# RFFI_pwrCtrl_Integrated_2021-05-11.net
KiCad netlist of a schematic drawn in EasyEDA
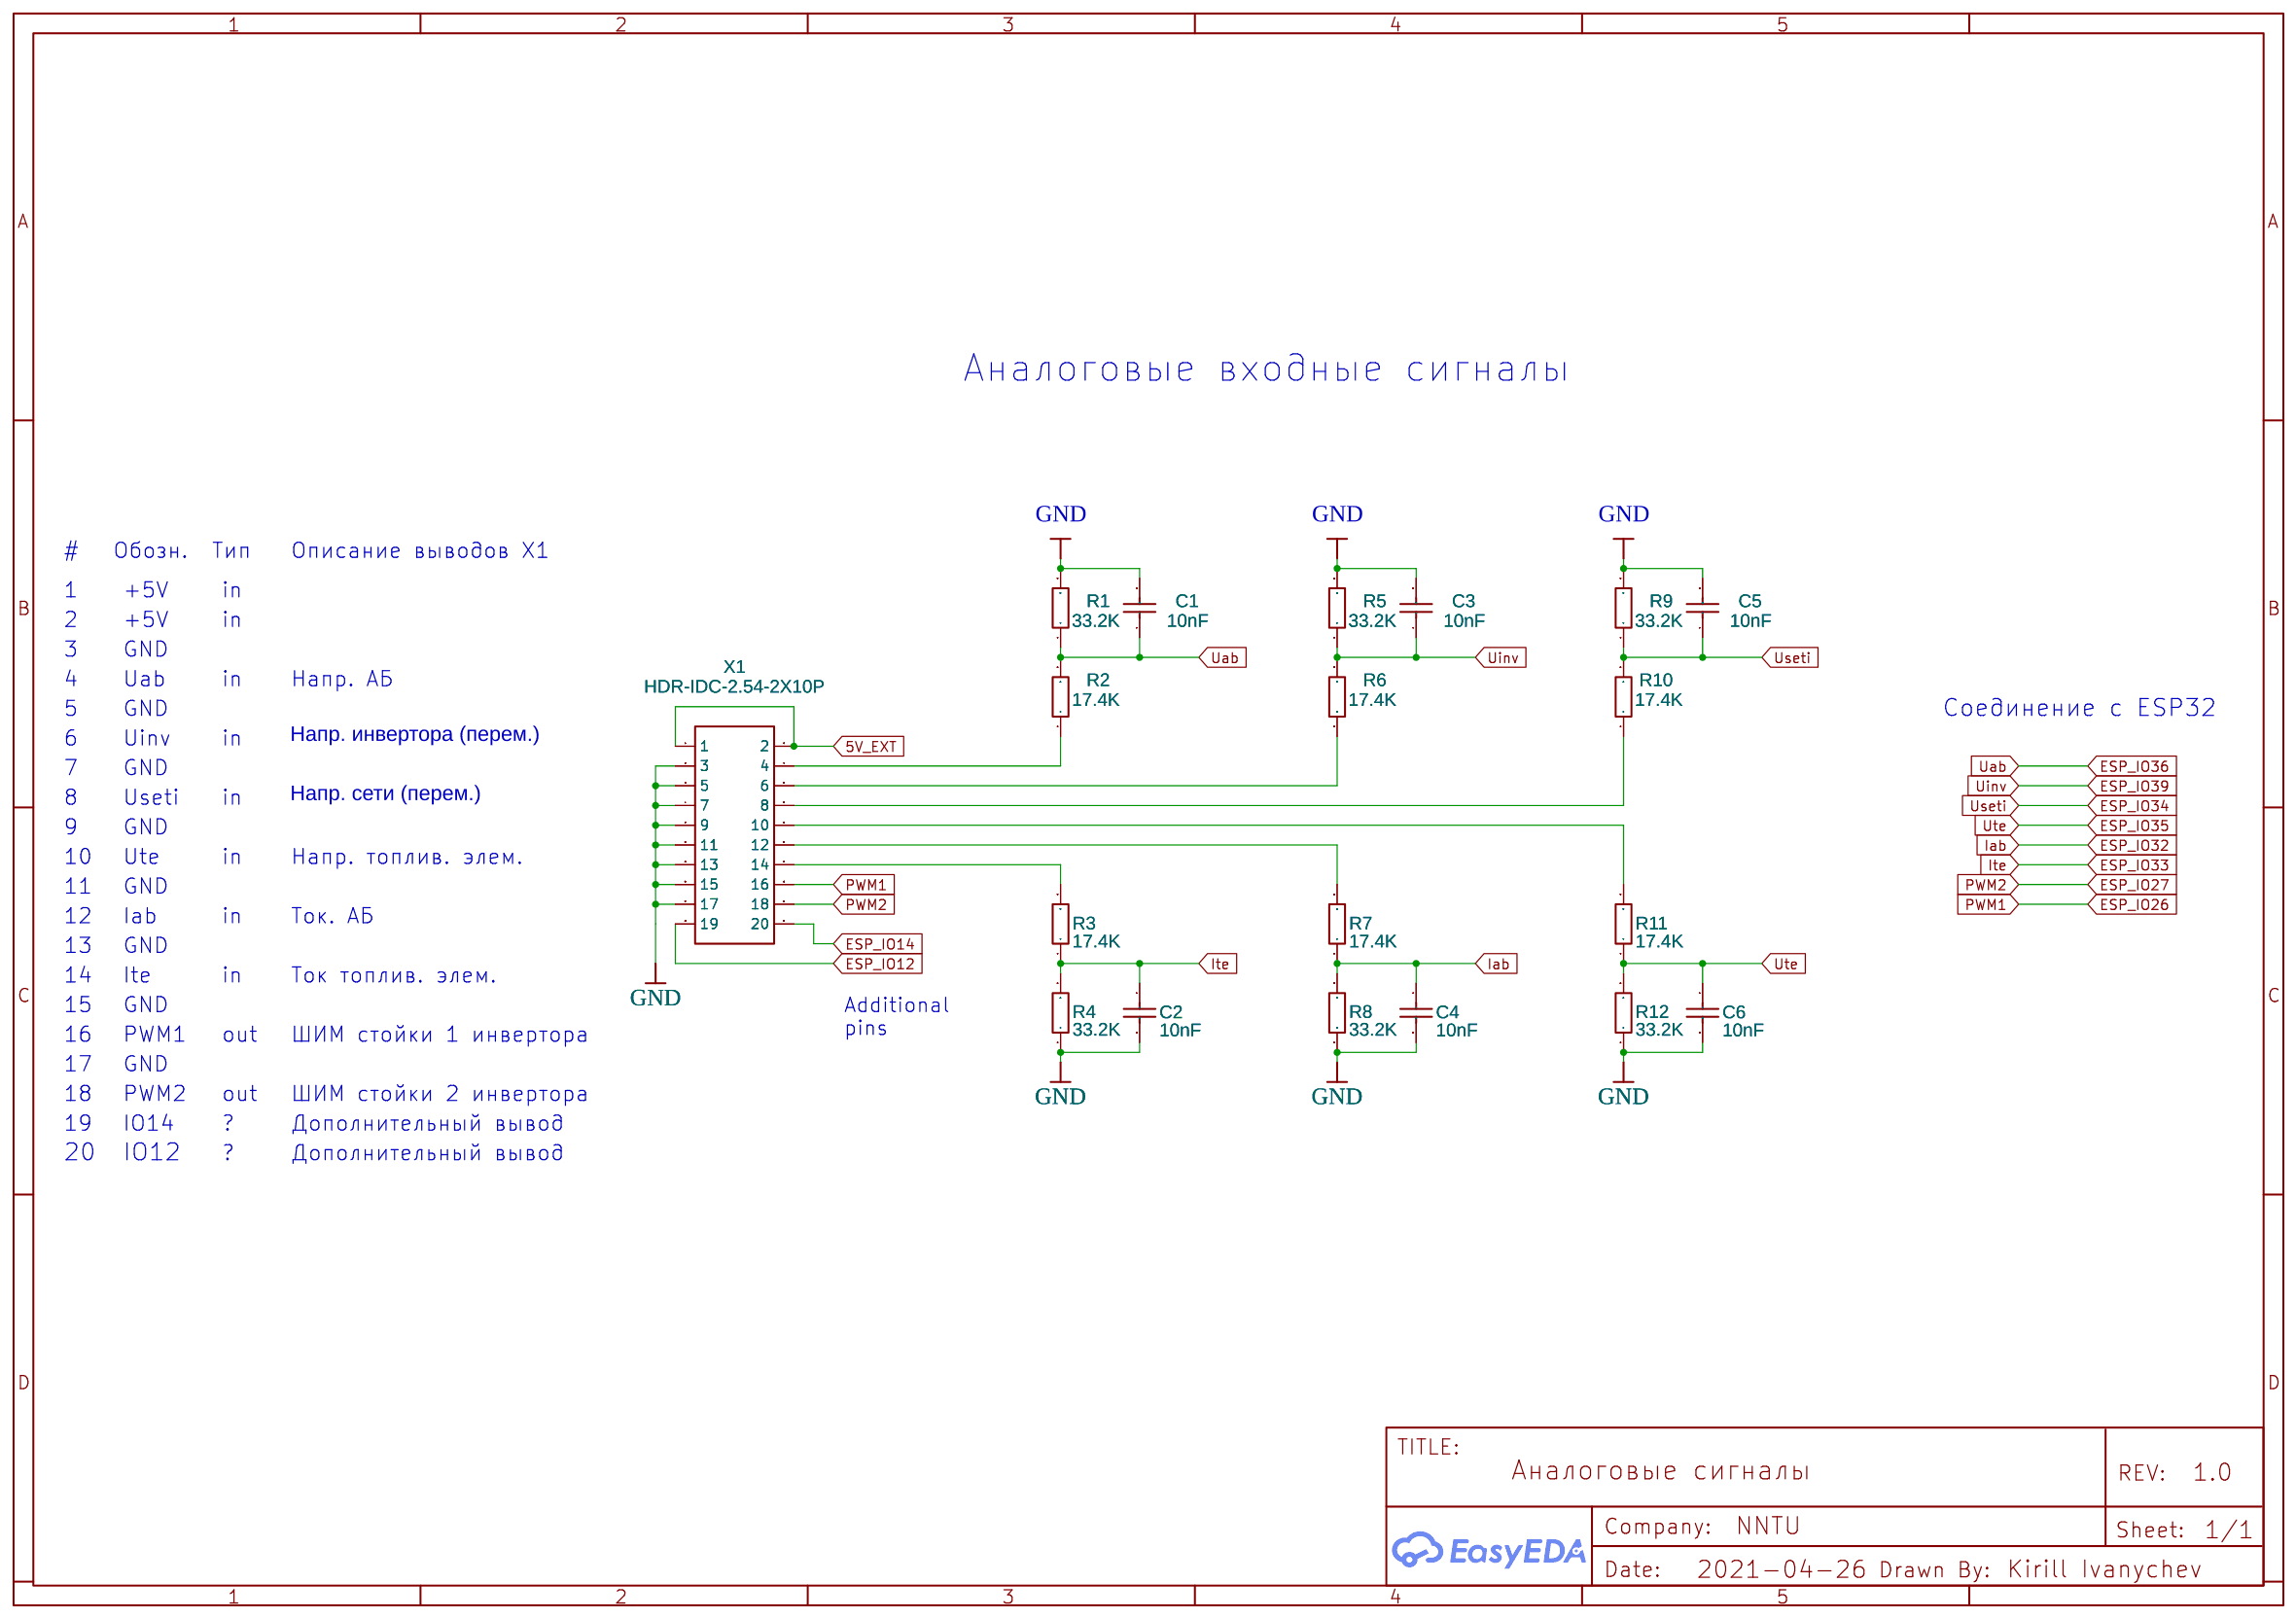
[diagram p0: Analog Signals]
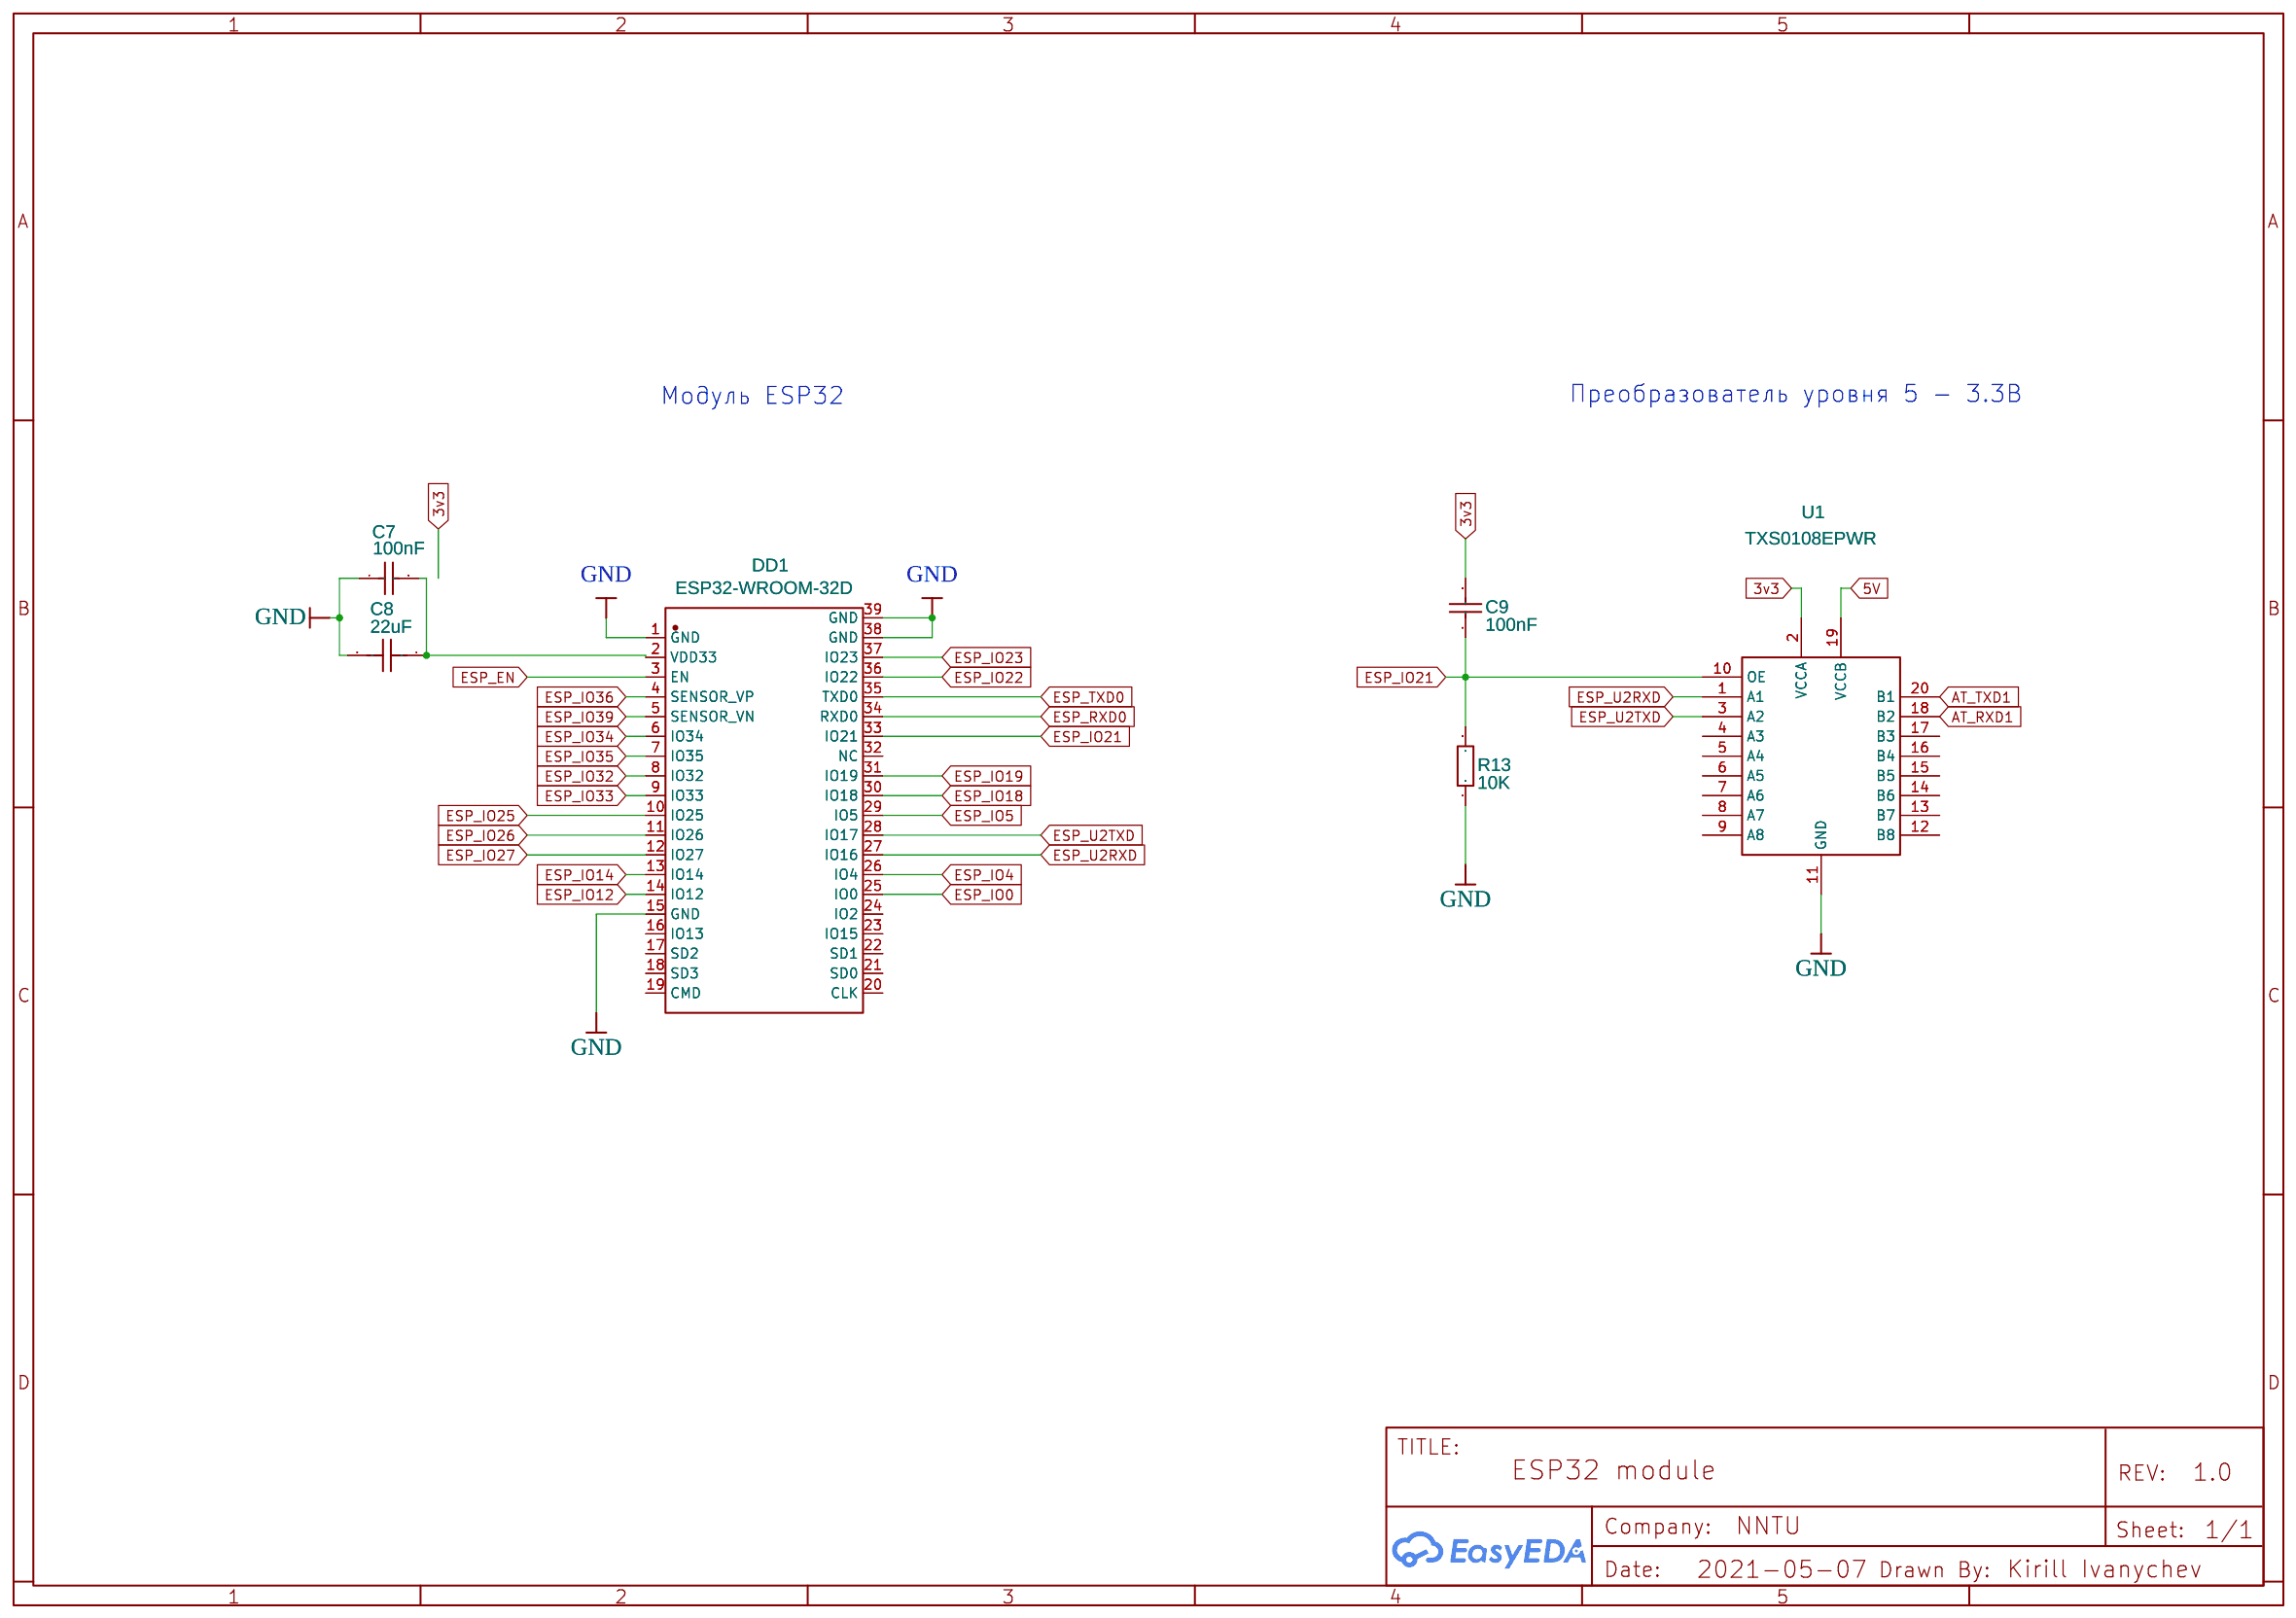
[diagram p1: ESP32 module]
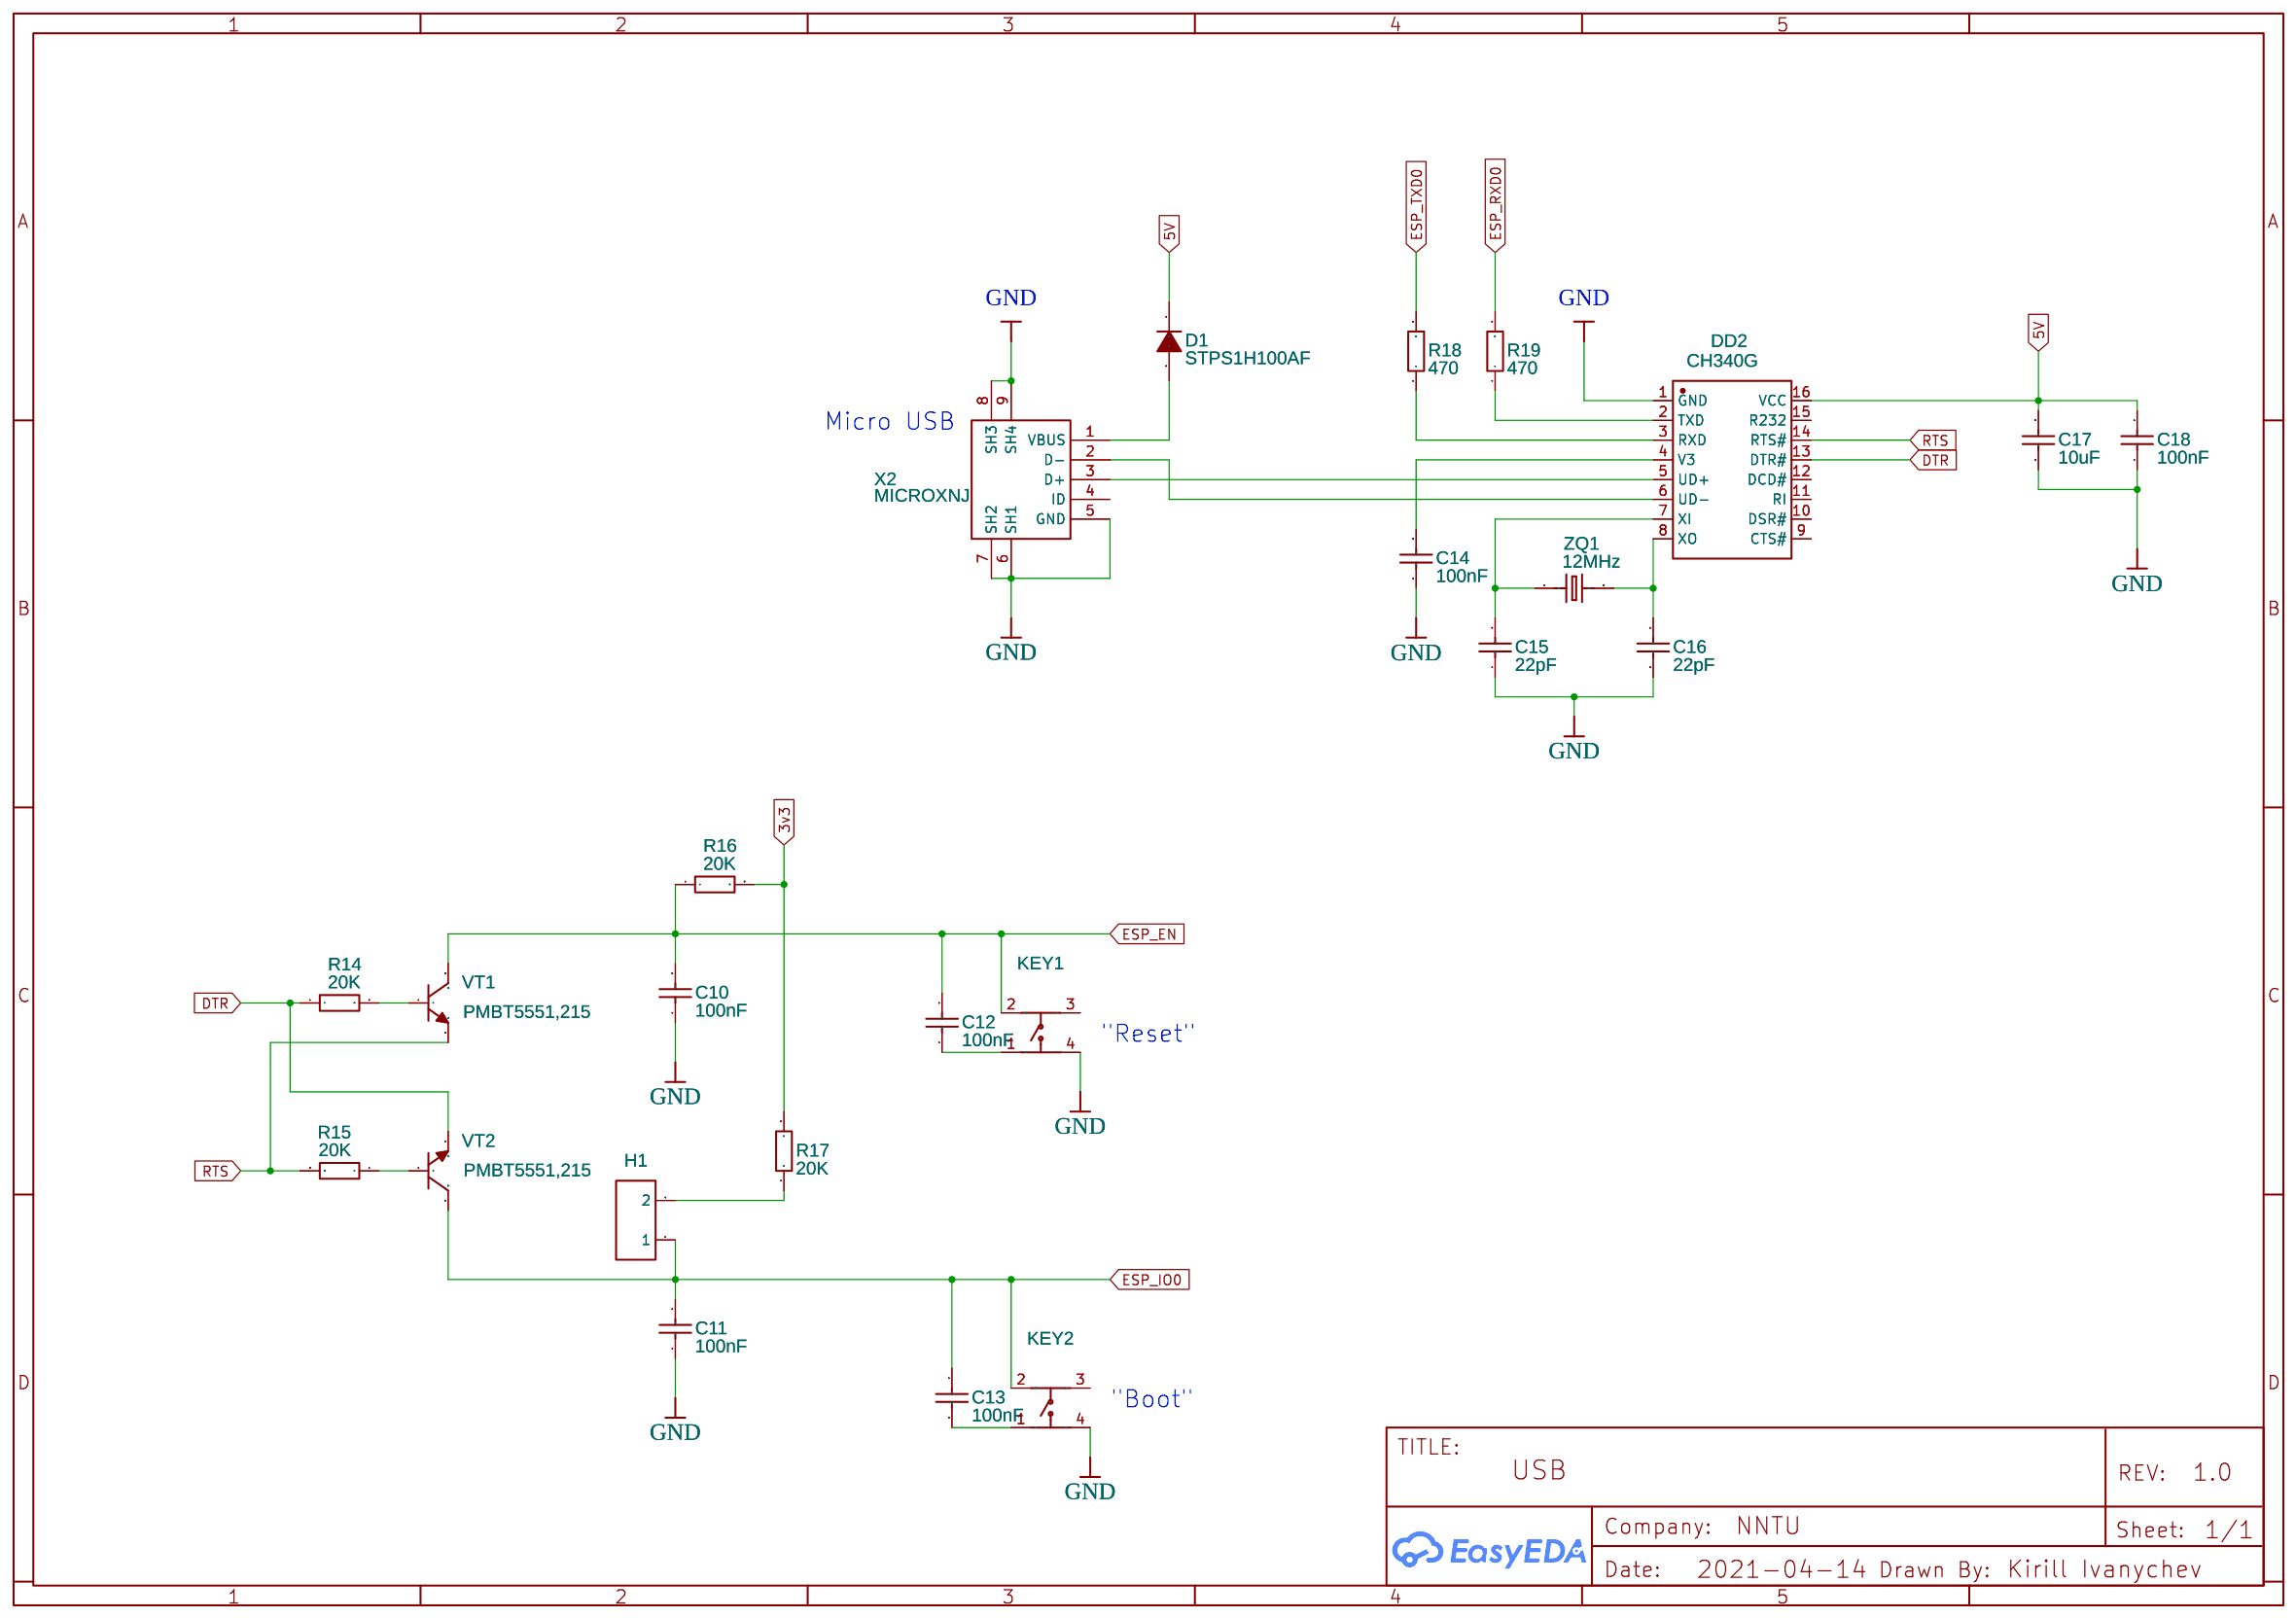
[diagram p2: USB]
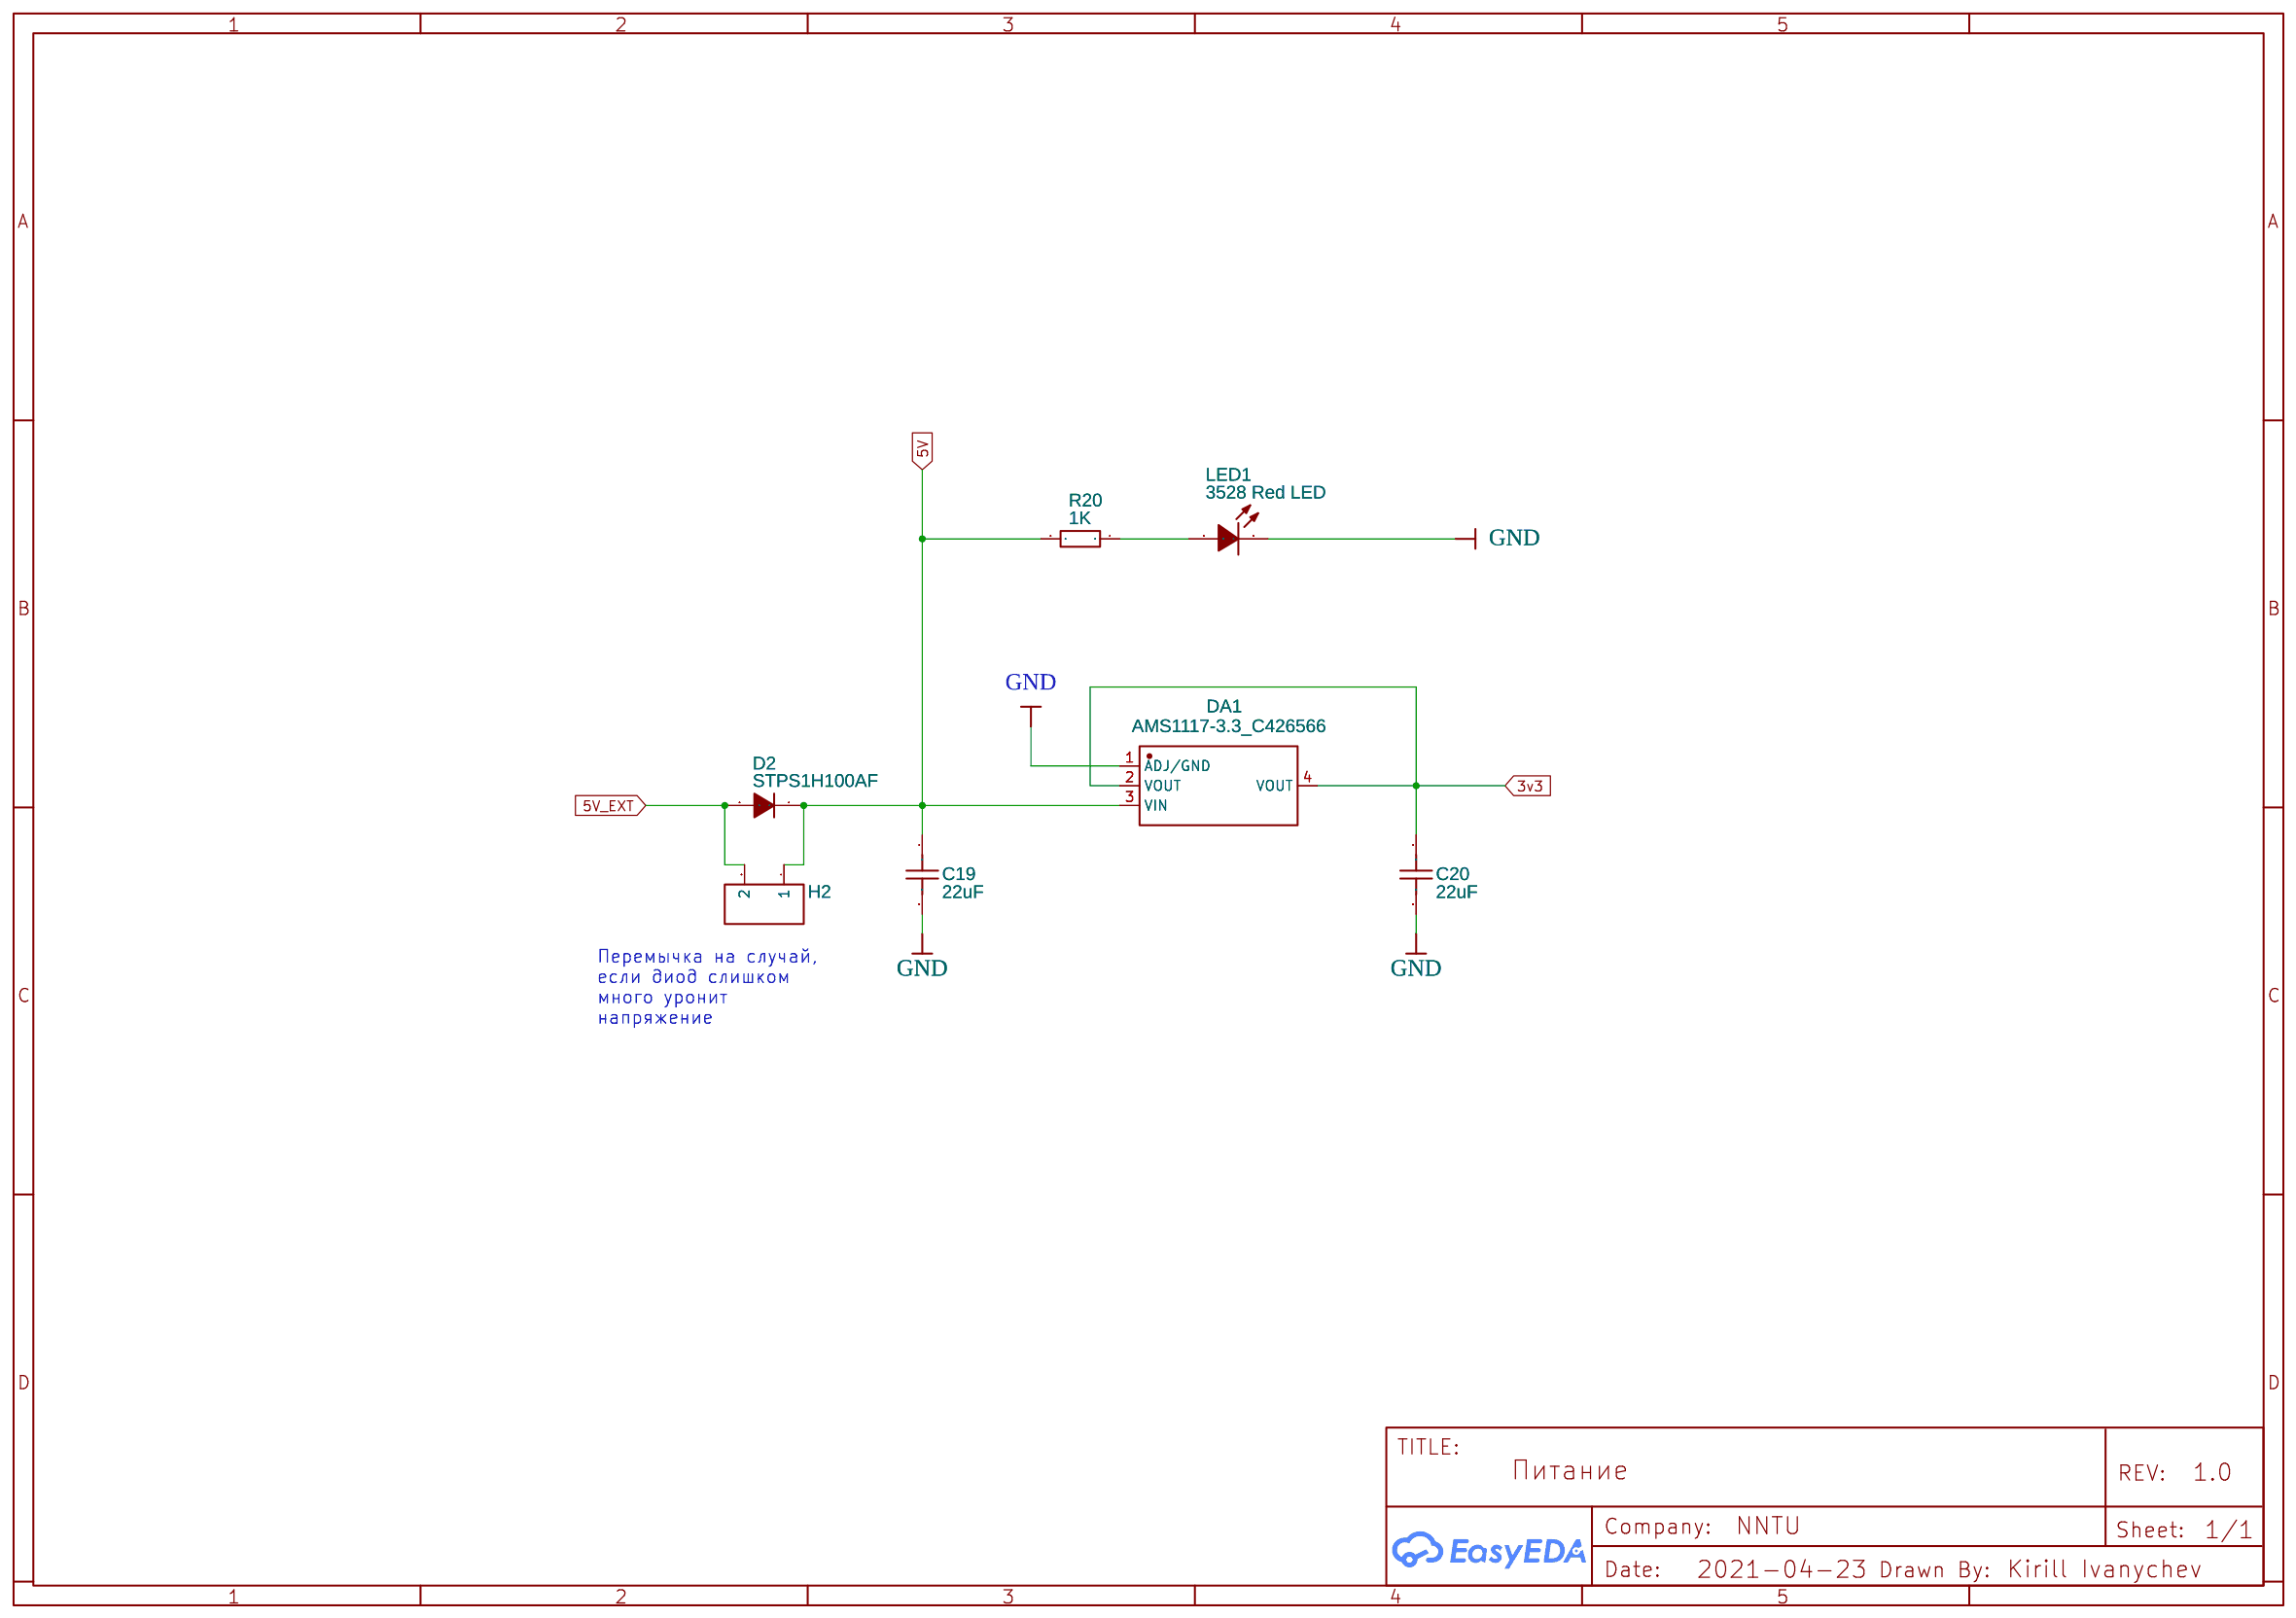
[diagram p3: Power]
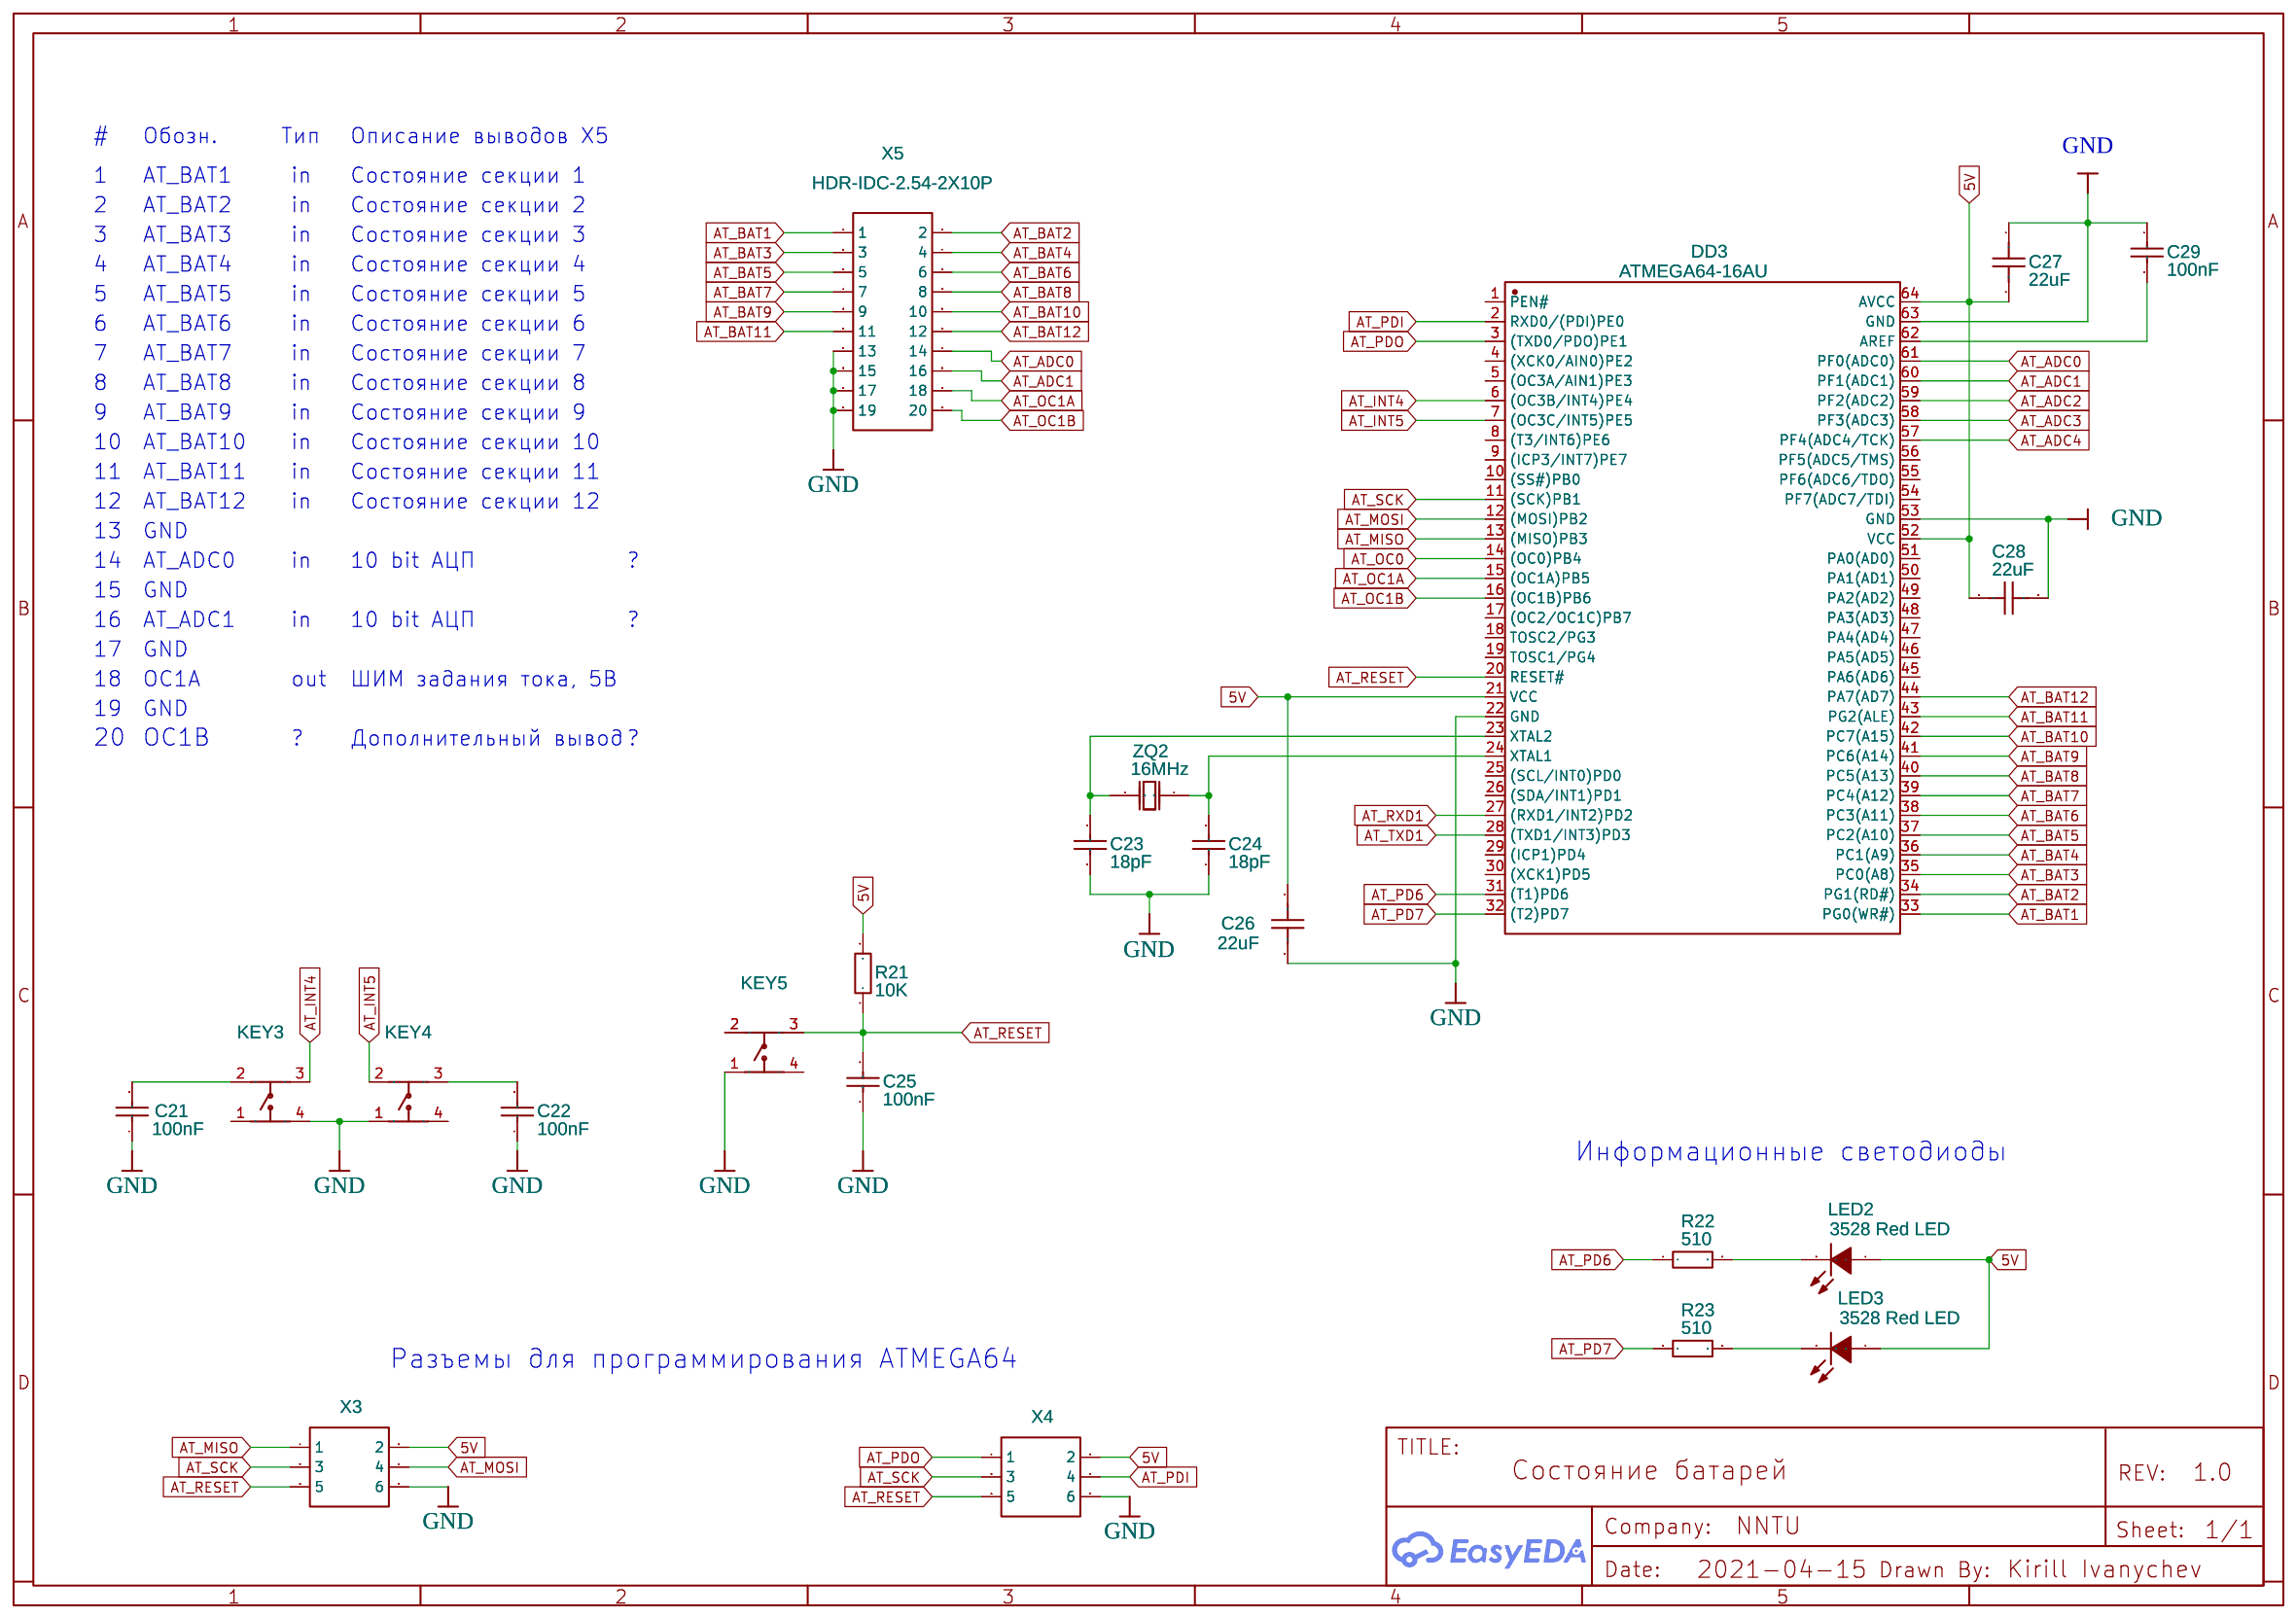
[diagram p4: Batteries]
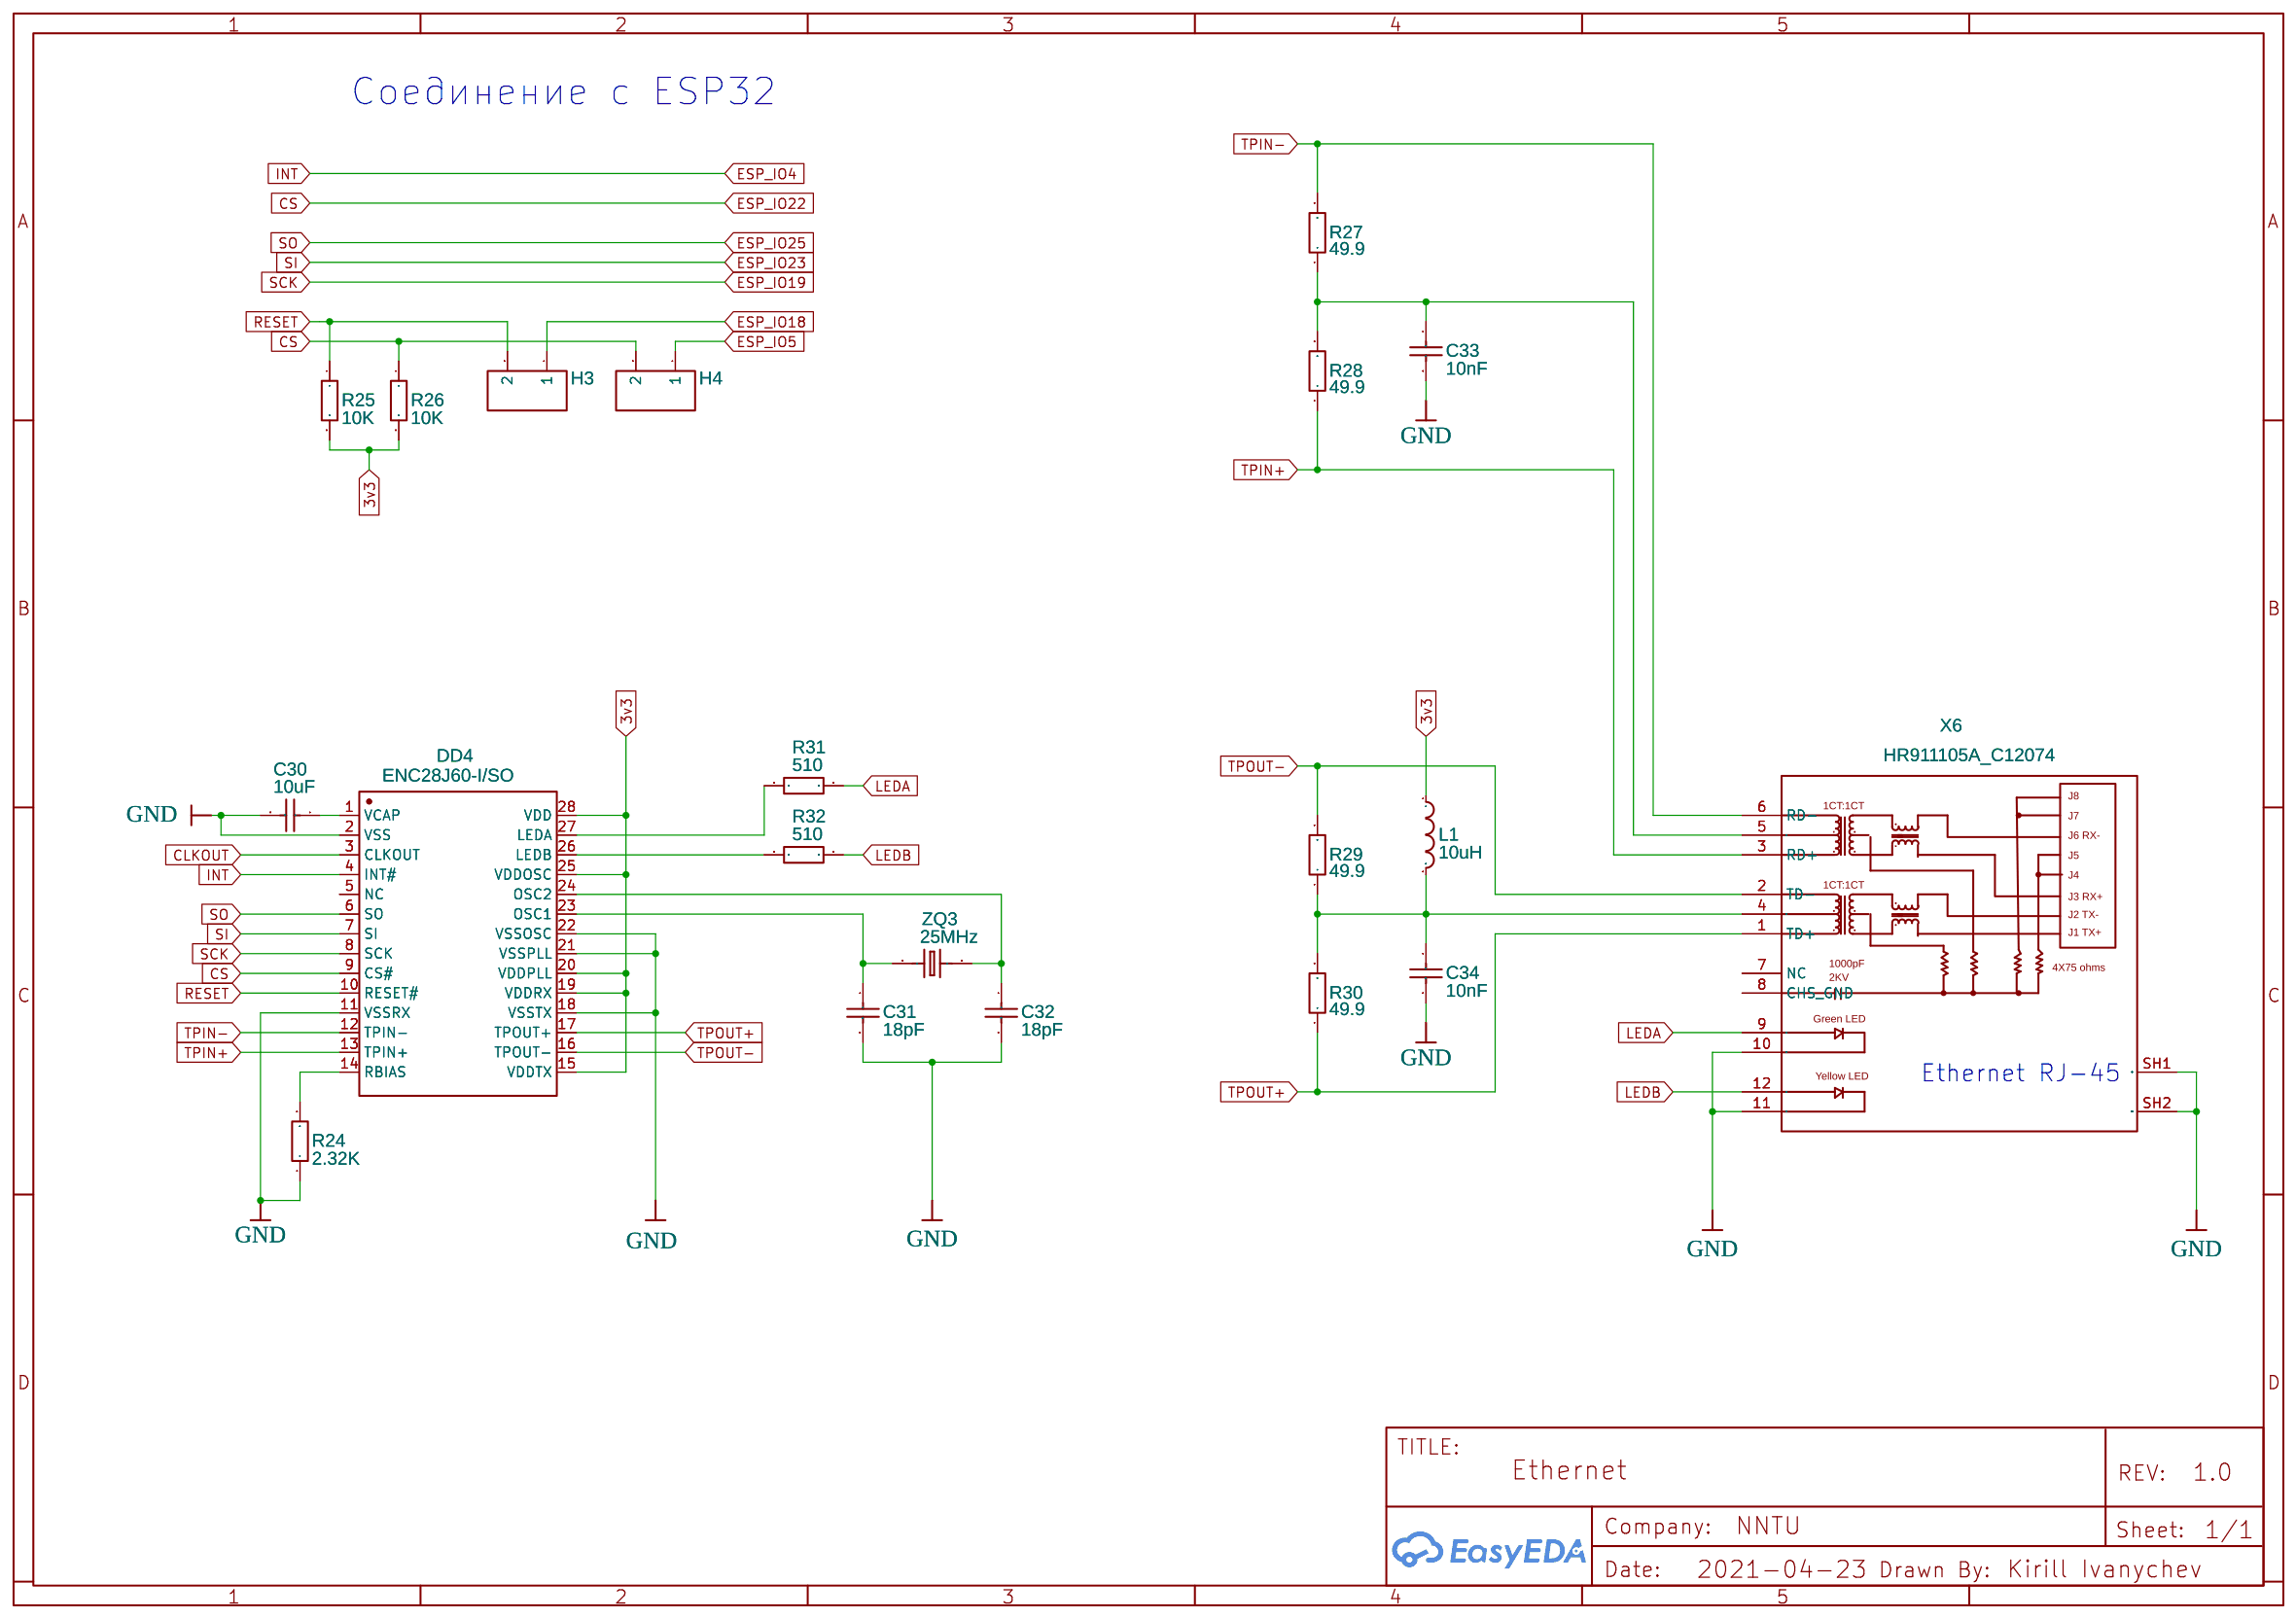
[diagram p5: Ethernet]

(export (version "E")
  (design (tool "Eeschema 10.0.6"))
  (components
    (comp (ref "C1")
      (value "10nF")
      (fields
        (field (name "BOM_Manufacturer Part") "1206B103K500NT")
        (field (name "BOM_Supplier Part") "C1846")
      )
      (libsource (lib "") (part "1206B103K500NT"))
    )
    (comp (ref "C2")
      (value "10nF")
      (fields
        (field (name "BOM_Manufacturer Part") "1206B103K500NT")
        (field (name "BOM_Supplier Part") "C1846")
      )
      (libsource (lib "") (part "1206B103K500NT_1"))
    )
    (comp (ref "C3")
      (value "10nF")
      (fields
        (field (name "BOM_Manufacturer Part") "1206B103K500NT")
        (field (name "BOM_Supplier Part") "C1846")
      )
      (libsource (lib "") (part "1206B103K500NT"))
    )
    (comp (ref "C4")
      (value "10nF")
      (fields
        (field (name "BOM_Manufacturer Part") "1206B103K500NT")
        (field (name "BOM_Supplier Part") "C1846")
      )
      (libsource (lib "") (part "1206B103K500NT_1"))
    )
    (comp (ref "C5")
      (value "10nF")
      (fields
        (field (name "BOM_Manufacturer Part") "1206B103K500NT")
        (field (name "BOM_Supplier Part") "C1846")
      )
      (libsource (lib "") (part "1206B103K500NT"))
    )
    (comp (ref "C6")
      (value "10nF")
      (fields
        (field (name "BOM_Manufacturer Part") "1206B103K500NT")
        (field (name "BOM_Supplier Part") "C1846")
      )
      (libsource (lib "") (part "1206B103K500NT_1"))
    )
    (comp (ref "R1")
      (value "33.2K")
      (fields
        (field (name "BOM_Manufacturer Part") "0603WAF3322T5E")
        (field (name "BOM_Supplier Part") "C23003")
      )
      (libsource (lib "") (part "0603WAF3322T5E"))
    )
    (comp (ref "R2")
      (value "17.4K")
      (fields
        (field (name "BOM_Manufacturer Part") "0402WGF1742TCE")
        (field (name "BOM_Supplier Part") "C26957")
      )
      (libsource (lib "") (part "0402WGF1742TCE"))
    )
    (comp (ref "R3")
      (value "17.4K")
      (fields
        (field (name "BOM_Manufacturer Part") "0402WGF1742TCE")
        (field (name "BOM_Supplier Part") "C26957")
      )
      (libsource (lib "") (part "0402WGF1742TCE"))
    )
    (comp (ref "R4")
      (value "33.2K")
      (fields
        (field (name "BOM_Manufacturer Part") "0603WAF3322T5E")
        (field (name "BOM_Supplier Part") "C23003")
      )
      (libsource (lib "") (part "0603WAF3322T5E"))
    )
    (comp (ref "R5")
      (value "33.2K")
      (fields
        (field (name "BOM_Manufacturer Part") "0603WAF3322T5E")
        (field (name "BOM_Supplier Part") "C23003")
      )
      (libsource (lib "") (part "0603WAF3322T5E"))
    )
    (comp (ref "R6")
      (value "17.4K")
      (fields
        (field (name "BOM_Manufacturer Part") "0402WGF1742TCE")
        (field (name "BOM_Supplier Part") "C26957")
      )
      (libsource (lib "") (part "0402WGF1742TCE"))
    )
    (comp (ref "R7")
      (value "17.4K")
      (fields
        (field (name "BOM_Manufacturer Part") "0402WGF1742TCE")
        (field (name "BOM_Supplier Part") "C26957")
      )
      (libsource (lib "") (part "0402WGF1742TCE"))
    )
    (comp (ref "R8")
      (value "33.2K")
      (fields
        (field (name "BOM_Manufacturer Part") "0603WAF3322T5E")
        (field (name "BOM_Supplier Part") "C23003")
      )
      (libsource (lib "") (part "0603WAF3322T5E"))
    )
    (comp (ref "R9")
      (value "33.2K")
      (fields
        (field (name "BOM_Manufacturer Part") "0603WAF3322T5E")
        (field (name "BOM_Supplier Part") "C23003")
      )
      (libsource (lib "") (part "0603WAF3322T5E"))
    )
    (comp (ref "R10")
      (value "17.4K")
      (fields
        (field (name "BOM_Manufacturer Part") "0402WGF1742TCE")
        (field (name "BOM_Supplier Part") "C26957")
      )
      (libsource (lib "") (part "0402WGF1742TCE"))
    )
    (comp (ref "R11")
      (value "17.4K")
      (fields
        (field (name "BOM_Manufacturer Part") "0402WGF1742TCE")
        (field (name "BOM_Supplier Part") "C26957")
      )
      (libsource (lib "") (part "0402WGF1742TCE"))
    )
    (comp (ref "R12")
      (value "33.2K")
      (fields
        (field (name "BOM_Manufacturer Part") "0603WAF3322T5E")
        (field (name "BOM_Supplier Part") "C23003")
      )
      (libsource (lib "") (part "0603WAF3322T5E"))
    )
    (comp (ref "X1")
      (value "HDR-IDC-2.54-2X10P")
      (fields
        (field (name "BOM_Manufacturer Part") "IDC Box 2.54mm 2X10P　Straight")
        (field (name "BOM_Supplier Part") "C3405")
      )
      (libsource (lib "") (part "HDR-IDC-2.54-2X10P"))
    )
    (comp (ref "C7")
      (value "100nF")
      (fields
        (field (name "BOM_Manufacturer Part") "CL21B104JBCNNNC")
        (field (name "BOM_Supplier Part") "C62912")
      )
      (libsource (lib "") (part "CL21B104JBCNNNC"))
    )
    (comp (ref "C8")
      (value "22uF")
      (fields
        (field (name "BOM_Manufacturer Part") "CL21A226MQQNNNE")
        (field (name "BOM_Supplier Part") "C5674")
      )
      (libsource (lib "") (part "CL21A226MQQNNNE"))
    )
    (comp (ref "C9")
      (value "100nF")
      (fields
        (field (name "BOM_Manufacturer Part") "CL21B104JBCNNNC")
        (field (name "BOM_Supplier Part") "C62912")
      )
      (libsource (lib "") (part "CL21B104JBCNNNC_1"))
    )
    (comp (ref "DD1")
      (value "ESP32-WROOM-32D")
      (fields (field (name "BOM_Supplier Part") "C473012"))
      (libsource (lib "") (part "ESP32-WROOM-32D"))
    )
    (comp (ref "R13")
      (value "10K")
      (fields
        (field (name "BOM_Manufacturer Part") "ARG03FTC1002")
        (field (name "BOM_Supplier Part") "C217687")
      )
      (libsource (lib "") (part "ARG03FTC1002"))
    )
    (comp (ref "U1")
      (value "TXS0108EPWR")
      (fields (field (name "BOM_Supplier Part") "C17206"))
      (libsource (lib "") (part "TXS0108EPWR"))
    )
    (comp (ref "C10")
      (value "100nF")
      (fields
        (field (name "BOM_Manufacturer Part") "CL21B104JBCNNNC")
        (field (name "BOM_Supplier Part") "C62912")
      )
      (libsource (lib "") (part "CL21B104JBCNNNC"))
    )
    (comp (ref "C11")
      (value "100nF")
      (fields
        (field (name "BOM_Manufacturer Part") "CL21B104JBCNNNC")
        (field (name "BOM_Supplier Part") "C62912")
      )
      (libsource (lib "") (part "CL21B104JBCNNNC"))
    )
    (comp (ref "C12")
      (value "100nF")
      (fields
        (field (name "BOM_Manufacturer Part") "CL21B104JBCNNNC")
        (field (name "BOM_Supplier Part") "C62912")
      )
      (libsource (lib "") (part "CL21B104JBCNNNC"))
    )
    (comp (ref "C13")
      (value "100nF")
      (fields
        (field (name "BOM_Manufacturer Part") "CL21B104JBCNNNC")
        (field (name "BOM_Supplier Part") "C62912")
      )
      (libsource (lib "") (part "CL21B104JBCNNNC"))
    )
    (comp (ref "C14")
      (value "100nF")
      (fields
        (field (name "BOM_Manufacturer Part") "CL21B104JBCNNNC")
        (field (name "BOM_Supplier Part") "C62912")
      )
      (libsource (lib "") (part "CL21B104JBCNNNC"))
    )
    (comp (ref "C15")
      (value "22pF")
      (fields
        (field (name "BOM_Manufacturer Part") "CL10C220JB8NNNC")
        (field (name "BOM_Supplier Part") "C1653")
      )
      (libsource (lib "") (part "CL10C220JB8NNNC"))
    )
    (comp (ref "C16")
      (value "22pF")
      (fields
        (field (name "BOM_Manufacturer Part") "CL10C220JB8NNNC")
        (field (name "BOM_Supplier Part") "C1653")
      )
      (libsource (lib "") (part "CL10C220JB8NNNC"))
    )
    (comp (ref "C17")
      (value "10uF")
      (fields
        (field (name "BOM_Manufacturer Part") "CL31B106KOHNNNE")
        (field (name "BOM_Supplier Part") "C47971")
      )
      (libsource (lib "") (part "CL31B106KOHNNNE"))
    )
    (comp (ref "C18")
      (value "100nF")
      (fields
        (field (name "BOM_Manufacturer Part") "CL21B104JBCNNNC")
        (field (name "BOM_Supplier Part") "C62912")
      )
      (libsource (lib "") (part "CL21B104JBCNNNC"))
    )
    (comp (ref "D1")
      (value "STPS1H100AF")
      (fields (field (name "BOM_Supplier Part") "C361044"))
      (libsource (lib "") (part "STPS1H100AF"))
    )
    (comp (ref "DD2")
      (value "CH340G")
      (fields (field (name "BOM_Supplier Part") "C14267"))
      (libsource (lib "") (part "CH340G"))
    )
    (comp (ref "H1")
      (value "Header-Male-2.54_1x2")
      (fields (field (name "BOM_Manufacturer Part") "826629-2") (field (name "BOM_Supplier Part") "C86471"))
      (libsource (lib "") (part "Header-Male-2.54_1x2"))
    )
    (comp (ref "KEY1")
      (value "TSA063G50-250")
      (fields (field (name "BOM_Supplier Part") "C294565"))
      (libsource (lib "") (part "TSA063G50-250"))
    )
    (comp (ref "KEY2")
      (value "TSA063G50-250")
      (fields (field (name "BOM_Supplier Part") "C294565"))
      (libsource (lib "") (part "TSA063G50-250"))
    )
    (comp (ref "R14")
      (value "20K")
      (fields
        (field (name "BOM_Manufacturer Part") "0805W8F2002T5E")
        (field (name "BOM_Supplier Part") "C4328")
      )
      (libsource (lib "") (part "0805W8F2002T5E"))
    )
    (comp (ref "R15")
      (value "20K")
      (fields
        (field (name "BOM_Manufacturer Part") "0805W8F2002T5E")
        (field (name "BOM_Supplier Part") "C4328")
      )
      (libsource (lib "") (part "0805W8F2002T5E_1"))
    )
    (comp (ref "R16")
      (value "20K")
      (fields
        (field (name "BOM_Manufacturer Part") "0805W8F2002T5E")
        (field (name "BOM_Supplier Part") "C4328")
      )
      (libsource (lib "") (part "0805W8F2002T5E"))
    )
    (comp (ref "R17")
      (value "20K")
      (fields
        (field (name "BOM_Manufacturer Part") "0805W8F2002T5E")
        (field (name "BOM_Supplier Part") "C4328")
      )
      (libsource (lib "") (part "0805W8F2002T5E_2"))
    )
    (comp (ref "R18")
      (value "470")
      (fields
        (field (name "BOM_Manufacturer Part") "1206W4J0471T5E")
        (field (name "BOM_Supplier Part") "C25383")
      )
      (libsource (lib "") (part "1206W4J0471T5E"))
    )
    (comp (ref "R19")
      (value "470")
      (fields
        (field (name "BOM_Manufacturer Part") "1206W4J0471T5E")
        (field (name "BOM_Supplier Part") "C25383")
      )
      (libsource (lib "") (part "1206W4J0471T5E"))
    )
    (comp (ref "VT1")
      (value "PMBT5551,215")
      (fields (field (name "BOM_Supplier Part") "C75557"))
      (libsource (lib "") (part "PMBT5551,215"))
    )
    (comp (ref "VT2")
      (value "PMBT5551,215")
      (fields (field (name "BOM_Supplier Part") "C75557"))
      (libsource (lib "") (part "PMBT5551,215_1"))
    )
    (comp (ref "X2")
      (value "MICROXNJ")
      (fields (field (name "BOM_Manufacturer Part") "MicroXNJ") (field (name "BOM_Supplier Part") "C404969"))
      (libsource (lib "") (part "MICROXNJ"))
    )
    (comp (ref "ZQ1")
      (value "12MHz")
      (fields
        (field (name "BOM_Manufacturer Part") "HC-49S12MHz20pF30PPM")
        (field (name "BOM_Supplier Part") "C127674")
      )
      (libsource (lib "") (part "HC-49S12MHZ20PF30PPM"))
    )
    (comp (ref "C19")
      (value "22uF")
      (fields
        (field (name "BOM_Manufacturer Part") "CL21A226MQQNNNE")
        (field (name "BOM_Supplier Part") "C5674")
      )
      (libsource (lib "") (part "CL21A226MQQNNNE"))
    )
    (comp (ref "C20")
      (value "22uF")
      (fields
        (field (name "BOM_Manufacturer Part") "CL21A226MQQNNNE")
        (field (name "BOM_Supplier Part") "C5674")
      )
      (libsource (lib "") (part "CL21A226MQQNNNE"))
    )
    (comp (ref "D2")
      (value "STPS1H100AF")
      (fields (field (name "BOM_Supplier Part") "C361044"))
      (libsource (lib "") (part "STPS1H100AF"))
    )
    (comp (ref "DA1")
      (value "AMS1117-3.3_C426566")
      (fields
        (field (name "BOM_Manufacturer Part") "AMS1117-3.3")
        (field (name "BOM_Supplier Part") "C426566")
      )
      (libsource (lib "") (part "AMS1117-3.3_C426566"))
    )
    (comp (ref "H2")
      (value "Header-Male-2.54_1x2")
      (fields (field (name "BOM_Manufacturer Part") "826629-2") (field (name "BOM_Supplier Part") "C86471"))
      (libsource (lib "") (part "Header-Male-2.54_1x2"))
    )
    (comp (ref "LED1")
      (value "3528 Red LED")
      (fields (field (name "BOM_Supplier Part") "C2305"))
      (libsource (lib "") (part "3528 Red LED"))
    )
    (comp (ref "R20")
      (value "1K")
      (fields
        (field (name "BOM_Manufacturer Part") "TC0525F1001T5E")
        (field (name "BOM_Supplier Part") "C75781")
      )
      (libsource (lib "") (part "TC0525F1001T5E"))
    )
    (comp (ref "C21")
      (value "100nF")
      (fields
        (field (name "BOM_Manufacturer Part") "CL21B104JBCNNNC")
        (field (name "BOM_Supplier Part") "C62912")
      )
      (libsource (lib "") (part "CL21B104JBCNNNC_1"))
    )
    (comp (ref "C22")
      (value "100nF")
      (fields
        (field (name "BOM_Manufacturer Part") "CL21B104JBCNNNC")
        (field (name "BOM_Supplier Part") "C62912")
      )
      (libsource (lib "") (part "CL21B104JBCNNNC_1"))
    )
    (comp (ref "C23")
      (value "18pF")
      (fields
        (field (name "BOM_Manufacturer Part") "0402CG180J500NT")
        (field (name "BOM_Supplier Part") "C1549")
      )
      (libsource (lib "") (part "0402CG180J500NT"))
    )
    (comp (ref "C24")
      (value "18pF")
      (fields
        (field (name "BOM_Manufacturer Part") "0402CG180J500NT")
        (field (name "BOM_Supplier Part") "C1549")
      )
      (libsource (lib "") (part "0402CG180J500NT_1"))
    )
    (comp (ref "C25")
      (value "100nF")
      (fields
        (field (name "BOM_Manufacturer Part") "CL21B104JBCNNNC")
        (field (name "BOM_Supplier Part") "C62912")
      )
      (libsource (lib "") (part "CL21B104JBCNNNC_1"))
    )
    (comp (ref "C26")
      (value "22uF")
      (fields
        (field (name "BOM_Manufacturer Part") "CL21A226MQQNNNE")
        (field (name "BOM_Supplier Part") "C5674")
      )
      (libsource (lib "") (part "CL21A226MQQNNNE"))
    )
    (comp (ref "C27")
      (value "22uF")
      (fields
        (field (name "BOM_Manufacturer Part") "CL21A226MQQNNNE")
        (field (name "BOM_Supplier Part") "C5674")
      )
      (libsource (lib "") (part "CL21A226MQQNNNE"))
    )
    (comp (ref "C28")
      (value "22uF")
      (fields
        (field (name "BOM_Manufacturer Part") "CL21A226MQQNNNE")
        (field (name "BOM_Supplier Part") "C5674")
      )
      (libsource (lib "") (part "CL21A226MQQNNNE_1"))
    )
    (comp (ref "C29")
      (value "100nF")
      (fields
        (field (name "BOM_Manufacturer Part") "CL21B104JBCNNNC")
        (field (name "BOM_Supplier Part") "C62912")
      )
      (libsource (lib "") (part "CL21B104JBCNNNC"))
    )
    (comp (ref "DD3")
      (value "ATMEGA64-16AU")
      (fields (field (name "BOM_Supplier Part") "C219170"))
      (libsource (lib "") (part "ATMEGA64-16AU"))
    )
    (comp (ref "KEY3")
      (value "TSA063G50-250")
      (fields (field (name "BOM_Supplier Part") "C294565"))
      (libsource (lib "") (part "TSA063G50-250"))
    )
    (comp (ref "KEY4")
      (value "TSA063G50-250")
      (fields (field (name "BOM_Supplier Part") "C294565"))
      (libsource (lib "") (part "TSA063G50-250"))
    )
    (comp (ref "KEY5")
      (value "TSA063G50-250")
      (fields (field (name "BOM_Supplier Part") "C294565"))
      (libsource (lib "") (part "TSA063G50-250"))
    )
    (comp (ref "LED2")
      (value "3528 Red LED")
      (fields (field (name "BOM_Supplier Part") "C2305"))
      (libsource (lib "") (part "3528 Red LED"))
    )
    (comp (ref "LED3")
      (value "3528 Red LED")
      (fields (field (name "BOM_Supplier Part") "C2305"))
      (libsource (lib "") (part "3528 Red LED"))
    )
    (comp (ref "R21")
      (value "10K")
      (fields
        (field (name "BOM_Manufacturer Part") "ARG03FTC1002")
        (field (name "BOM_Supplier Part") "C217687")
      )
      (libsource (lib "") (part "ARG03FTC1002"))
    )
    (comp (ref "R22")
      (value "510")
      (fields
        (field (name "BOM_Manufacturer Part") "1206W4J0511T5E")
        (field (name "BOM_Supplier Part") "C25386")
      )
      (libsource (lib "") (part "1206W4J0511T5E"))
    )
    (comp (ref "R23")
      (value "510")
      (fields
        (field (name "BOM_Manufacturer Part") "1206W4J0511T5E")
        (field (name "BOM_Supplier Part") "C25386")
      )
      (libsource (lib "") (part "1206W4J0511T5E"))
    )
    (comp (ref "X3")
      (value "Header-Male-2.54_2x3")
      (fields (field (name "BOM_Supplier Part") "C65114"))
      (libsource (lib "") (part "Header-Male-2.54_2x3"))
    )
    (comp (ref "X4")
      (value "Header-Male-2.54_2x3")
      (fields (field (name "BOM_Supplier Part") "C65114"))
      (libsource (lib "") (part "Header-Male-2.54_2x3"))
    )
    (comp (ref "X5")
      (value "HDR-IDC-2.54-2X10P")
      (fields
        (field (name "BOM_Manufacturer Part") "IDC Box 2.54mm 2X10P　Straight")
        (field (name "BOM_Supplier Part") "C3405")
      )
      (libsource (lib "") (part "HDR-IDC-2.54-2X10P"))
    )
    (comp (ref "ZQ2")
      (value "16MHz")
      (fields
        (field (name "BOM_Manufacturer Part") "X49SD16MSB2SI")
        (field (name "BOM_Supplier Part") "C188202")
      )
      (libsource (lib "") (part "X49SD16MSB2SI"))
    )
    (comp (ref "C30")
      (value "10uF")
      (fields
        (field (name "BOM_Manufacturer Part") "CL31B106KOHNNNE")
        (field (name "BOM_Supplier Part") "C47971")
      )
      (libsource (lib "") (part "CL31B106KOHNNNE"))
    )
    (comp (ref "C31")
      (value "18pF")
      (fields
        (field (name "BOM_Manufacturer Part") "0402CG180J500NT")
        (field (name "BOM_Supplier Part") "C1549")
      )
      (libsource (lib "") (part "0402CG180J500NT"))
    )
    (comp (ref "C32")
      (value "18pF")
      (fields
        (field (name "BOM_Manufacturer Part") "0402CG180J500NT")
        (field (name "BOM_Supplier Part") "C1549")
      )
      (libsource (lib "") (part "0402CG180J500NT"))
    )
    (comp (ref "C33")
      (value "10nF")
      (fields
        (field (name "BOM_Manufacturer Part") "CL21B103KBANNNC")
        (field (name "BOM_Supplier Part") "C1710")
      )
      (libsource (lib "") (part "CL21B103KBANNNC"))
    )
    (comp (ref "C34")
      (value "10nF")
      (fields
        (field (name "BOM_Manufacturer Part") "CL21B103KBANNNC")
        (field (name "BOM_Supplier Part") "C1710")
      )
      (libsource (lib "") (part "CL21B103KBANNNC"))
    )
    (comp (ref "DD4")
      (value "ENC28J60-I/SO")
      (fields (field (name "BOM_Supplier Part") "C47351"))
      (libsource (lib "") (part "ENC28J60-I/SO"))
    )
    (comp (ref "H3")
      (value "Header-Male-2.54_1x2")
      (fields (field (name "BOM_Manufacturer Part") "826629-2") (field (name "BOM_Supplier Part") "C86471"))
      (libsource (lib "") (part "Header-Male-2.54_1x2"))
    )
    (comp (ref "H4")
      (value "Header-Male-2.54_1x2")
      (fields (field (name "BOM_Manufacturer Part") "826629-2") (field (name "BOM_Supplier Part") "C86471"))
      (libsource (lib "") (part "Header-Male-2.54_1x2"))
    )
    (comp (ref "L1")
      (value "10uH")
      (fields
        (field (name "BOM_Manufacturer Part") "CMI321609X100KT")
        (field (name "BOM_Supplier Part") "C1051")
      )
      (libsource (lib "") (part "CMI321609X100KT"))
    )
    (comp (ref "R24")
      (value "2.32K")
      (fields
        (field (name "BOM_Manufacturer Part") "1206W4F2321T5E")
        (field (name "BOM_Supplier Part") "C247348")
      )
      (libsource (lib "") (part "1206W4F2321T5E"))
    )
    (comp (ref "R25")
      (value "10K")
      (fields
        (field (name "BOM_Manufacturer Part") "ARG03FTC1002")
        (field (name "BOM_Supplier Part") "C217687")
      )
      (libsource (lib "") (part "ARG03FTC1002"))
    )
    (comp (ref "R26")
      (value "10K")
      (fields
        (field (name "BOM_Manufacturer Part") "ARG03FTC1002")
        (field (name "BOM_Supplier Part") "C217687")
      )
      (libsource (lib "") (part "ARG03FTC1002"))
    )
    (comp (ref "R27")
      (value "49.9")
      (fields
        (field (name "BOM_Manufacturer Part") "0805W8F499JT5E")
        (field (name "BOM_Supplier Part") "C17720")
      )
      (libsource (lib "") (part "0805W8F499JT5E"))
    )
    (comp (ref "R28")
      (value "49.9")
      (fields
        (field (name "BOM_Manufacturer Part") "0805W8F499JT5E")
        (field (name "BOM_Supplier Part") "C17720")
      )
      (libsource (lib "") (part "0805W8F499JT5E"))
    )
    (comp (ref "R29")
      (value "49.9")
      (fields
        (field (name "BOM_Manufacturer Part") "0805W8F499JT5E")
        (field (name "BOM_Supplier Part") "C17720")
      )
      (libsource (lib "") (part "0805W8F499JT5E"))
    )
    (comp (ref "R30")
      (value "49.9")
      (fields
        (field (name "BOM_Manufacturer Part") "0805W8F499JT5E")
        (field (name "BOM_Supplier Part") "C17720")
      )
      (libsource (lib "") (part "0805W8F499JT5E"))
    )
    (comp (ref "R31")
      (value "510")
      (fields
        (field (name "BOM_Manufacturer Part") "1206W4J0511T5E")
        (field (name "BOM_Supplier Part") "C25386")
      )
      (libsource (lib "") (part "1206W4J0511T5E"))
    )
    (comp (ref "R32")
      (value "510")
      (fields
        (field (name "BOM_Manufacturer Part") "1206W4J0511T5E")
        (field (name "BOM_Supplier Part") "C25386")
      )
      (libsource (lib "") (part "1206W4J0511T5E"))
    )
    (comp (ref "X6")
      (value "HR911105A_C12074")
      (fields (field (name "BOM_Manufacturer Part") "HR911105A") (field (name "BOM_Supplier Part") "C12074"))
      (libsource (lib "") (part "HR911105A_C12074"))
    )
    (comp (ref "ZQ3")
      (value "25MHz")
      (fields
        (field (name "BOM_Manufacturer Part") "X49SD25MSD2SI")
        (field (name "BOM_Supplier Part") "C130152")
      )
      (libsource (lib "") (part "X49SD25MSD2SI"))
    )
  )
  (nets
    (net (code "1") (name "3v3") (class "Default")
      (node (ref "C20") (pin "1") (pinfunction "1_1") (pintype "unspecified"))
      (node (ref "C9") (pin "1") (pinfunction "1_1") (pintype "input"))
      (node (ref "DA1") (pin "2") (pinfunction "VOUT_2") (pintype "unspecified"))
      (node (ref "DA1") (pin "4") (pinfunction "VOUT_4") (pintype "unspecified"))
      (node (ref "DD4") (pin "15") (pinfunction "VDDTX_15") (pintype "unspecified"))
      (node (ref "DD4") (pin "19") (pinfunction "VDDRX_19") (pintype "unspecified"))
      (node (ref "DD4") (pin "20") (pinfunction "VDDPLL_20") (pintype "unspecified"))
      (node (ref "DD4") (pin "25") (pinfunction "VDDOSC_25") (pintype "unspecified"))
      (node (ref "DD4") (pin "28") (pinfunction "VDD_28") (pintype "unspecified"))
      (node (ref "L1") (pin "1") (pinfunction "1_1") (pintype "unspecified"))
      (node (ref "R16") (pin "2") (pinfunction "2_2") (pintype "input"))
      (node (ref "R17") (pin "2") (pinfunction "2_2") (pintype "input"))
      (node (ref "R25") (pin "2") (pinfunction "2_2") (pintype "unspecified"))
      (node (ref "R26") (pin "2") (pinfunction "2_2") (pintype "unspecified"))
      (node (ref "U1") (pin "2") (pinfunction "VCCA_2") (pintype "unspecified"))
    )
    (net (code "2") (name "5V") (class "Default")
      (node (ref "C17") (pin "2") (pinfunction "2_2") (pintype "input"))
      (node (ref "C18") (pin "2") (pinfunction "2_2") (pintype "input"))
      (node (ref "C19") (pin "1") (pinfunction "1_1") (pintype "unspecified"))
      (node (ref "C26") (pin "1") (pinfunction "1_1") (pintype "unspecified"))
      (node (ref "C27") (pin "2") (pinfunction "2_2") (pintype "unspecified"))
      (node (ref "C28") (pin "1") (pinfunction "1_1") (pintype "unspecified"))
      (node (ref "D1") (pin "1") (pinfunction "K_1") (pintype "unspecified"))
      (node (ref "D2") (pin "1") (pinfunction "K_1") (pintype "unspecified"))
      (node (ref "DA1") (pin "3") (pinfunction "VIN_3") (pintype "unspecified"))
      (node (ref "DD2") (pin "16") (pinfunction "VCC_16") (pintype "unspecified"))
      (node (ref "DD3") (pin "21") (pinfunction "VCC_21") (pintype "unspecified"))
      (node (ref "DD3") (pin "52") (pinfunction "VCC_52") (pintype "unspecified"))
      (node (ref "DD3") (pin "64") (pinfunction "AVCC_64") (pintype "unspecified"))
      (node (ref "H2") (pin "1") (pinfunction "1_1") (pintype "unspecified"))
      (node (ref "LED2") (pin "1") (pinfunction "A_1") (pintype "unspecified"))
      (node (ref "LED3") (pin "1") (pinfunction "A_1") (pintype "unspecified"))
      (node (ref "R20") (pin "2") (pinfunction "2_2") (pintype "input"))
      (node (ref "R21") (pin "2") (pinfunction "2_2") (pintype "unspecified"))
      (node (ref "U1") (pin "19") (pinfunction "VCCB_19") (pintype "unspecified"))
      (node (ref "X3") (pin "2") (pinfunction "2_2") (pintype "input"))
      (node (ref "X4") (pin "2") (pinfunction "2_2") (pintype "input"))
    )
    (net (code "3") (name "5V_EXT") (class "Default")
      (node (ref "D2") (pin "2") (pinfunction "A_2") (pintype "unspecified"))
      (node (ref "H2") (pin "2") (pinfunction "2_2") (pintype "unspecified"))
      (node (ref "X1") (pin "1") (pinfunction "1_1") (pintype "unspecified"))
      (node (ref "X1") (pin "2") (pinfunction "2_2") (pintype "unspecified"))
    )
    (net (code "4") (name "AT_ADC0") (class "Default")
      (node (ref "DD3") (pin "61") (pinfunction "PF0(ADC0)_61") (pintype "unspecified"))
      (node (ref "X5") (pin "14") (pinfunction "14_14") (pintype "unspecified"))
    )
    (net (code "5") (name "AT_ADC1") (class "Default")
      (node (ref "DD3") (pin "60") (pinfunction "PF1(ADC1)_60") (pintype "unspecified"))
      (node (ref "X5") (pin "16") (pinfunction "16_16") (pintype "unspecified"))
    )
    (net (code "6") (name "AT_ADC2") (class "Default")
      (node (ref "DD3") (pin "59") (pinfunction "PF2(ADC2)_59") (pintype "unspecified"))
    )
    (net (code "7") (name "AT_ADC3") (class "Default")
      (node (ref "DD3") (pin "58") (pinfunction "PF3(ADC3)_58") (pintype "unspecified"))
    )
    (net (code "8") (name "AT_ADC4") (class "Default")
      (node (ref "DD3") (pin "57") (pinfunction "PF4(ADC4/TCK)_57") (pintype "unspecified"))
    )
    (net (code "9") (name "AT_BAT1") (class "Default")
      (node (ref "DD3") (pin "33") (pinfunction "PG0(WR#)_33") (pintype "unspecified"))
      (node (ref "X5") (pin "1") (pinfunction "1_1") (pintype "unspecified"))
    )
    (net (code "10") (name "AT_BAT2") (class "Default")
      (node (ref "DD3") (pin "34") (pinfunction "PG1(RD#)_34") (pintype "unspecified"))
      (node (ref "X5") (pin "2") (pinfunction "2_2") (pintype "unspecified"))
    )
    (net (code "11") (name "AT_BAT3") (class "Default")
      (node (ref "DD3") (pin "35") (pinfunction "PC0(A8)_35") (pintype "unspecified"))
      (node (ref "X5") (pin "3") (pinfunction "3_3") (pintype "unspecified"))
    )
    (net (code "12") (name "AT_BAT4") (class "Default")
      (node (ref "DD3") (pin "36") (pinfunction "PC1(A9)_36") (pintype "unspecified"))
      (node (ref "X5") (pin "4") (pinfunction "4_4") (pintype "unspecified"))
    )
    (net (code "13") (name "AT_BAT5") (class "Default")
      (node (ref "DD3") (pin "37") (pinfunction "PC2(A10)_37") (pintype "unspecified"))
      (node (ref "X5") (pin "5") (pinfunction "5_5") (pintype "unspecified"))
    )
    (net (code "14") (name "AT_BAT6") (class "Default")
      (node (ref "DD3") (pin "38") (pinfunction "PC3(A11)_38") (pintype "unspecified"))
      (node (ref "X5") (pin "6") (pinfunction "6_6") (pintype "unspecified"))
    )
    (net (code "15") (name "AT_BAT7") (class "Default")
      (node (ref "DD3") (pin "39") (pinfunction "PC4(A12)_39") (pintype "unspecified"))
      (node (ref "X5") (pin "7") (pinfunction "7_7") (pintype "unspecified"))
    )
    (net (code "16") (name "AT_BAT8") (class "Default")
      (node (ref "DD3") (pin "40") (pinfunction "PC5(A13)_40") (pintype "unspecified"))
      (node (ref "X5") (pin "8") (pinfunction "8_8") (pintype "unspecified"))
    )
    (net (code "17") (name "AT_BAT9") (class "Default")
      (node (ref "DD3") (pin "41") (pinfunction "PC6(A14)_41") (pintype "unspecified"))
      (node (ref "X5") (pin "9") (pinfunction "9_9") (pintype "unspecified"))
    )
    (net (code "18") (name "AT_BAT10") (class "Default")
      (node (ref "DD3") (pin "42") (pinfunction "PC7(A15)_42") (pintype "unspecified"))
      (node (ref "X5") (pin "10") (pinfunction "10_10") (pintype "unspecified"))
    )
    (net (code "19") (name "AT_BAT11") (class "Default")
      (node (ref "DD3") (pin "43") (pinfunction "PG2(ALE)_43") (pintype "unspecified"))
      (node (ref "X5") (pin "11") (pinfunction "11_11") (pintype "unspecified"))
    )
    (net (code "20") (name "AT_BAT12") (class "Default")
      (node (ref "DD3") (pin "44") (pinfunction "PA7(AD7)_44") (pintype "unspecified"))
      (node (ref "X5") (pin "12") (pinfunction "12_12") (pintype "unspecified"))
    )
    (net (code "21") (name "AT_INT4") (class "Default")
      (node (ref "DD3") (pin "6") (pinfunction "(OC3B/INT4)PE4_6") (pintype "unspecified"))
      (node (ref "KEY3") (pin "3") (pinfunction "3_3") (pintype "unspecified"))
    )
    (net (code "22") (name "AT_INT5") (class "Default")
      (node (ref "DD3") (pin "7") (pinfunction "(OC3C/INT5)PE5_7") (pintype "unspecified"))
      (node (ref "KEY4") (pin "2") (pinfunction "2_2") (pintype "unspecified"))
    )
    (net (code "23") (name "AT_MISO") (class "Default")
      (node (ref "DD3") (pin "13") (pinfunction "(MISO)PB3_13") (pintype "unspecified"))
      (node (ref "X3") (pin "1") (pinfunction "1_1") (pintype "input"))
    )
    (net (code "24") (name "AT_MOSI") (class "Default")
      (node (ref "DD3") (pin "12") (pinfunction "(MOSI)PB2_12") (pintype "unspecified"))
      (node (ref "X3") (pin "4") (pinfunction "4_4") (pintype "input"))
    )
    (net (code "25") (name "AT_OC0") (class "Default")
      (node (ref "DD3") (pin "14") (pinfunction "(OC0)PB4_14") (pintype "unspecified"))
    )
    (net (code "26") (name "AT_OC1A") (class "Default")
      (node (ref "DD3") (pin "15") (pinfunction "(OC1A)PB5_15") (pintype "unspecified"))
      (node (ref "X5") (pin "18") (pinfunction "18_18") (pintype "unspecified"))
    )
    (net (code "27") (name "AT_OC1B") (class "Default")
      (node (ref "DD3") (pin "16") (pinfunction "(OC1B)PB6_16") (pintype "unspecified"))
      (node (ref "X5") (pin "20") (pinfunction "20_20") (pintype "unspecified"))
    )
    (net (code "28") (name "AT_PD6") (class "Default")
      (node (ref "DD3") (pin "31") (pinfunction "(T1)PD6_31") (pintype "unspecified"))
      (node (ref "R22") (pin "1") (pinfunction "1_1") (pintype "input"))
    )
    (net (code "29") (name "AT_PD7") (class "Default")
      (node (ref "DD3") (pin "32") (pinfunction "(T2)PD7_32") (pintype "unspecified"))
      (node (ref "R23") (pin "1") (pinfunction "1_1") (pintype "input"))
    )
    (net (code "30") (name "AT_PDI") (class "Default")
      (node (ref "DD3") (pin "2") (pinfunction "RXD0/(PDI)PE0_2") (pintype "unspecified"))
      (node (ref "X4") (pin "4") (pinfunction "4_4") (pintype "input"))
    )
    (net (code "31") (name "AT_PDO") (class "Default")
      (node (ref "DD3") (pin "3") (pinfunction "(TXD0/PDO)PE1_3") (pintype "unspecified"))
      (node (ref "X4") (pin "1") (pinfunction "1_1") (pintype "input"))
    )
    (net (code "32") (name "AT_RESET") (class "Default")
      (node (ref "C25") (pin "2") (pinfunction "2_2") (pintype "input"))
      (node (ref "DD3") (pin "20") (pinfunction "RESET#_20") (pintype "unspecified"))
      (node (ref "KEY5") (pin "3") (pinfunction "3_3") (pintype "unspecified"))
      (node (ref "R21") (pin "1") (pinfunction "1_1") (pintype "unspecified"))
      (node (ref "X3") (pin "5") (pinfunction "5_5") (pintype "input"))
      (node (ref "X4") (pin "5") (pinfunction "5_5") (pintype "input"))
    )
    (net (code "33") (name "AT_RXD1") (class "Default")
      (node (ref "DD3") (pin "27") (pinfunction "(RXD1/INT2)PD2_27") (pintype "unspecified"))
      (node (ref "U1") (pin "18") (pinfunction "B2_18") (pintype "unspecified"))
    )
    (net (code "34") (name "AT_SCK") (class "Default")
      (node (ref "DD3") (pin "11") (pinfunction "(SCK)PB1_11") (pintype "unspecified"))
      (node (ref "X3") (pin "3") (pinfunction "3_3") (pintype "input"))
      (node (ref "X4") (pin "3") (pinfunction "3_3") (pintype "input"))
    )
    (net (code "35") (name "AT_TXD1") (class "Default")
      (node (ref "DD3") (pin "28") (pinfunction "(TXD1/INT3)PD3_28") (pintype "unspecified"))
      (node (ref "U1") (pin "20") (pinfunction "B1_20") (pintype "unspecified"))
    )
    (net (code "36") (name "CLKOUT") (class "Default")
      (node (ref "DD4") (pin "3") (pinfunction "CLKOUT_3") (pintype "unspecified"))
    )
    (net (code "37") (name "CS") (class "Default")
      (node (ref "DD1") (pin "36") (pinfunction "IO22_36") (pintype "unspecified"))
      (node (ref "DD4") (pin "9") (pinfunction "CS#_9") (pintype "unspecified"))
      (node (ref "H4") (pin "2") (pinfunction "2_2") (pintype "unspecified"))
      (node (ref "R26") (pin "1") (pinfunction "1_1") (pintype "unspecified"))
    )
    (net (code "38") (name "DTR") (class "Default")
      (node (ref "DD2") (pin "13") (pinfunction "DTR#_13") (pintype "unspecified"))
      (node (ref "R14") (pin "1") (pinfunction "1_1") (pintype "input"))
      (node (ref "VT2") (pin "2") (pinfunction "2_2") (pintype "input"))
    )
    (net (code "39") (name "ESP_EN") (class "Default")
      (node (ref "C10") (pin "2") (pinfunction "2_2") (pintype "input"))
      (node (ref "C12") (pin "2") (pinfunction "2_2") (pintype "input"))
      (node (ref "DD1") (pin "3") (pinfunction "EN_3") (pintype "unspecified"))
      (node (ref "KEY1") (pin "2") (pinfunction "2_2") (pintype "unspecified"))
      (node (ref "R16") (pin "1") (pinfunction "1_1") (pintype "input"))
      (node (ref "VT1") (pin "3") (pinfunction "3_3") (pintype "input"))
    )
    (net (code "40") (name "ESP_IO0") (class "Default")
      (node (ref "C11") (pin "2") (pinfunction "2_2") (pintype "input"))
      (node (ref "C13") (pin "2") (pinfunction "2_2") (pintype "input"))
      (node (ref "DD1") (pin "25") (pinfunction "IO0_25") (pintype "unspecified"))
      (node (ref "H1") (pin "1") (pinfunction "1_1") (pintype "unspecified"))
      (node (ref "KEY2") (pin "2") (pinfunction "2_2") (pintype "unspecified"))
      (node (ref "VT2") (pin "3") (pinfunction "3_3") (pintype "input"))
    )
    (net (code "41") (name "ESP_IO4") (class "Default")
      (node (ref "DD1") (pin "26") (pinfunction "IO4_26") (pintype "unspecified"))
      (node (ref "DD4") (pin "4") (pinfunction "INT#_4") (pintype "unspecified"))
    )
    (net (code "42") (name "ESP_IO5") (class "Default")
      (node (ref "DD1") (pin "29") (pinfunction "IO5_29") (pintype "unspecified"))
      (node (ref "H4") (pin "1") (pinfunction "1_1") (pintype "unspecified"))
    )
    (net (code "43") (name "ESP_IO12") (class "Default")
      (node (ref "DD1") (pin "14") (pinfunction "IO12_14") (pintype "unspecified"))
      (node (ref "X1") (pin "19") (pinfunction "19_19") (pintype "unspecified"))
    )
    (net (code "44") (name "ESP_IO14") (class "Default")
      (node (ref "DD1") (pin "13") (pinfunction "IO14_13") (pintype "unspecified"))
      (node (ref "X1") (pin "20") (pinfunction "20_20") (pintype "unspecified"))
    )
    (net (code "45") (name "ESP_IO18") (class "Default")
      (node (ref "DD1") (pin "30") (pinfunction "IO18_30") (pintype "unspecified"))
      (node (ref "H3") (pin "1") (pinfunction "1_1") (pintype "unspecified"))
    )
    (net (code "46") (name "ESP_IO19") (class "Default")
      (node (ref "DD1") (pin "31") (pinfunction "IO19_31") (pintype "unspecified"))
      (node (ref "DD4") (pin "8") (pinfunction "SCK_8") (pintype "unspecified"))
    )
    (net (code "47") (name "ESP_IO21") (class "Default")
      (node (ref "C9") (pin "2") (pinfunction "2_2") (pintype "input"))
      (node (ref "DD1") (pin "33") (pinfunction "IO21_33") (pintype "unspecified"))
      (node (ref "R13") (pin "2") (pinfunction "2_2") (pintype "unspecified"))
      (node (ref "U1") (pin "10") (pinfunction "OE_10") (pintype "unspecified"))
    )
    (net (code "48") (name "ESP_IO23") (class "Default")
      (node (ref "DD1") (pin "37") (pinfunction "IO23_37") (pintype "unspecified"))
      (node (ref "DD4") (pin "7") (pinfunction "SI_7") (pintype "unspecified"))
    )
    (net (code "49") (name "ESP_IO25") (class "Default")
      (node (ref "DD1") (pin "10") (pinfunction "IO25_10") (pintype "unspecified"))
      (node (ref "DD4") (pin "6") (pinfunction "SO_6") (pintype "unspecified"))
    )
    (net (code "50") (name "ESP_IO26") (class "Default")
      (node (ref "DD1") (pin "11") (pinfunction "IO26_11") (pintype "unspecified"))
      (node (ref "X1") (pin "16") (pinfunction "16_16") (pintype "unspecified"))
    )
    (net (code "51") (name "ESP_IO27") (class "Default")
      (node (ref "DD1") (pin "12") (pinfunction "IO27_12") (pintype "unspecified"))
      (node (ref "X1") (pin "18") (pinfunction "18_18") (pintype "unspecified"))
    )
    (net (code "52") (name "ESP_IO32") (class "Default")
      (node (ref "C4") (pin "1") (pinfunction "1_1") (pintype "input"))
      (node (ref "DD1") (pin "8") (pinfunction "IO32_8") (pintype "unspecified"))
      (node (ref "R7") (pin "1") (pinfunction "1_1") (pintype "input"))
      (node (ref "R8") (pin "2") (pinfunction "2_2") (pintype "input"))
    )
    (net (code "53") (name "ESP_IO33") (class "Default")
      (node (ref "C2") (pin "1") (pinfunction "1_1") (pintype "input"))
      (node (ref "DD1") (pin "9") (pinfunction "IO33_9") (pintype "unspecified"))
      (node (ref "R3") (pin "1") (pinfunction "1_1") (pintype "input"))
      (node (ref "R4") (pin "2") (pinfunction "2_2") (pintype "input"))
    )
    (net (code "54") (name "ESP_IO34") (class "Default")
      (node (ref "C5") (pin "1") (pinfunction "1_1") (pintype "input"))
      (node (ref "DD1") (pin "6") (pinfunction "IO34_6") (pintype "unspecified"))
      (node (ref "R10") (pin "2") (pinfunction "2_2") (pintype "input"))
      (node (ref "R9") (pin "1") (pinfunction "1_1") (pintype "input"))
    )
    (net (code "55") (name "ESP_IO35") (class "Default")
      (node (ref "C6") (pin "1") (pinfunction "1_1") (pintype "input"))
      (node (ref "DD1") (pin "7") (pinfunction "IO35_7") (pintype "unspecified"))
      (node (ref "R11") (pin "1") (pinfunction "1_1") (pintype "input"))
      (node (ref "R12") (pin "2") (pinfunction "2_2") (pintype "input"))
    )
    (net (code "56") (name "ESP_IO36") (class "Default")
      (node (ref "C1") (pin "1") (pinfunction "1_1") (pintype "input"))
      (node (ref "DD1") (pin "4") (pinfunction "SENSOR_VP_4") (pintype "unspecified"))
      (node (ref "R1") (pin "1") (pinfunction "1_1") (pintype "input"))
      (node (ref "R2") (pin "2") (pinfunction "2_2") (pintype "input"))
    )
    (net (code "57") (name "ESP_IO39") (class "Default")
      (node (ref "C3") (pin "1") (pinfunction "1_1") (pintype "input"))
      (node (ref "DD1") (pin "5") (pinfunction "SENSOR_VN_5") (pintype "unspecified"))
      (node (ref "R5") (pin "1") (pinfunction "1_1") (pintype "input"))
      (node (ref "R6") (pin "2") (pinfunction "2_2") (pintype "input"))
    )
    (net (code "58") (name "ESP_RXD0") (class "Default")
      (node (ref "DD1") (pin "34") (pinfunction "RXD0_34") (pintype "unspecified"))
      (node (ref "R19") (pin "2") (pinfunction "2_2") (pintype "input"))
    )
    (net (code "59") (name "ESP_TXD0") (class "Default")
      (node (ref "DD1") (pin "35") (pinfunction "TXD0_35") (pintype "unspecified"))
      (node (ref "R18") (pin "2") (pinfunction "2_2") (pintype "input"))
    )
    (net (code "60") (name "ESP_U2RXD") (class "Default")
      (node (ref "DD1") (pin "27") (pinfunction "IO16_27") (pintype "unspecified"))
      (node (ref "U1") (pin "1") (pinfunction "A1_1") (pintype "unspecified"))
    )
    (net (code "61") (name "ESP_U2TXD") (class "Default")
      (node (ref "DD1") (pin "28") (pinfunction "IO17_28") (pintype "unspecified"))
      (node (ref "U1") (pin "3") (pinfunction "A2_3") (pintype "unspecified"))
    )
    (net (code "62") (name "GND") (class "Default")
      (node (ref "C1") (pin "2") (pinfunction "2_2") (pintype "input"))
      (node (ref "C10") (pin "1") (pinfunction "1_1") (pintype "input"))
      (node (ref "C11") (pin "1") (pinfunction "1_1") (pintype "input"))
      (node (ref "C14") (pin "1") (pinfunction "1_1") (pintype "input"))
      (node (ref "C15") (pin "1") (pinfunction "1_1") (pintype "input"))
      (node (ref "C16") (pin "1") (pinfunction "1_1") (pintype "input"))
      (node (ref "C17") (pin "1") (pinfunction "1_1") (pintype "input"))
      (node (ref "C18") (pin "1") (pinfunction "1_1") (pintype "input"))
      (node (ref "C19") (pin "2") (pinfunction "2_2") (pintype "unspecified"))
      (node (ref "C2") (pin "2") (pinfunction "2_2") (pintype "input"))
      (node (ref "C20") (pin "2") (pinfunction "2_2") (pintype "unspecified"))
      (node (ref "C21") (pin "1") (pinfunction "1_1") (pintype "input"))
      (node (ref "C22") (pin "1") (pinfunction "1_1") (pintype "input"))
      (node (ref "C23") (pin "2") (pinfunction "2_2") (pintype "input"))
      (node (ref "C24") (pin "1") (pinfunction "1_1") (pintype "input"))
      (node (ref "C25") (pin "1") (pinfunction "1_1") (pintype "input"))
      (node (ref "C26") (pin "2") (pinfunction "2_2") (pintype "unspecified"))
      (node (ref "C27") (pin "1") (pinfunction "1_1") (pintype "unspecified"))
      (node (ref "C28") (pin "2") (pinfunction "2_2") (pintype "unspecified"))
      (node (ref "C29") (pin "1") (pinfunction "1_1") (pintype "input"))
      (node (ref "C3") (pin "2") (pinfunction "2_2") (pintype "input"))
      (node (ref "C30") (pin "2") (pinfunction "2_2") (pintype "input"))
      (node (ref "C31") (pin "2") (pinfunction "2_2") (pintype "input"))
      (node (ref "C32") (pin "2") (pinfunction "2_2") (pintype "input"))
      (node (ref "C33") (pin "2") (pinfunction "2_2") (pintype "input"))
      (node (ref "C34") (pin "2") (pinfunction "2_2") (pintype "input"))
      (node (ref "C4") (pin "2") (pinfunction "2_2") (pintype "input"))
      (node (ref "C5") (pin "2") (pinfunction "2_2") (pintype "input"))
      (node (ref "C6") (pin "2") (pinfunction "2_2") (pintype "input"))
      (node (ref "C7") (pin "1") (pinfunction "1_1") (pintype "input"))
      (node (ref "C8") (pin "2") (pinfunction "2_2") (pintype "unspecified"))
      (node (ref "DA1") (pin "1") (pinfunction "ADJ/GND_1") (pintype "unspecified"))
      (node (ref "DD1") (pin "1") (pinfunction "GND_1") (pintype "unspecified"))
      (node (ref "DD1") (pin "15") (pinfunction "GND_15") (pintype "unspecified"))
      (node (ref "DD1") (pin "38") (pinfunction "GND_38") (pintype "unspecified"))
      (node (ref "DD1") (pin "39") (pinfunction "GND_39") (pintype "unspecified"))
      (node (ref "DD2") (pin "1") (pinfunction "GND_1") (pintype "unspecified"))
      (node (ref "DD3") (pin "22") (pinfunction "GND_22") (pintype "unspecified"))
      (node (ref "DD3") (pin "53") (pinfunction "GND_53") (pintype "unspecified"))
      (node (ref "DD3") (pin "63") (pinfunction "GND_63") (pintype "unspecified"))
      (node (ref "DD4") (pin "11") (pinfunction "VSSRX_11") (pintype "unspecified"))
      (node (ref "DD4") (pin "18") (pinfunction "VSSTX_18") (pintype "unspecified"))
      (node (ref "DD4") (pin "2") (pinfunction "VSS_2") (pintype "unspecified"))
      (node (ref "DD4") (pin "21") (pinfunction "VSSPLL_21") (pintype "unspecified"))
      (node (ref "DD4") (pin "22") (pinfunction "VSSOSC_22") (pintype "unspecified"))
      (node (ref "KEY1") (pin "4") (pinfunction "4_4") (pintype "unspecified"))
      (node (ref "KEY2") (pin "4") (pinfunction "4_4") (pintype "unspecified"))
      (node (ref "KEY3") (pin "4") (pinfunction "4_4") (pintype "unspecified"))
      (node (ref "KEY4") (pin "1") (pinfunction "1_1") (pintype "unspecified"))
      (node (ref "KEY5") (pin "1") (pinfunction "1_1") (pintype "unspecified"))
      (node (ref "LED1") (pin "2") (pinfunction "K_2") (pintype "unspecified"))
      (node (ref "R1") (pin "2") (pinfunction "2_2") (pintype "input"))
      (node (ref "R12") (pin "1") (pinfunction "1_1") (pintype "input"))
      (node (ref "R13") (pin "1") (pinfunction "1_1") (pintype "unspecified"))
      (node (ref "R24") (pin "1") (pinfunction "1_1") (pintype "unspecified"))
      (node (ref "R4") (pin "1") (pinfunction "1_1") (pintype "input"))
      (node (ref "R5") (pin "2") (pinfunction "2_2") (pintype "input"))
      (node (ref "R8") (pin "1") (pinfunction "1_1") (pintype "input"))
      (node (ref "R9") (pin "2") (pinfunction "2_2") (pintype "input"))
      (node (ref "U1") (pin "11") (pinfunction "GND_11") (pintype "unspecified"))
      (node (ref "X1") (pin "11") (pinfunction "11_11") (pintype "unspecified"))
      (node (ref "X1") (pin "13") (pinfunction "13_13") (pintype "unspecified"))
      (node (ref "X1") (pin "15") (pinfunction "15_15") (pintype "unspecified"))
      (node (ref "X1") (pin "17") (pinfunction "17_17") (pintype "unspecified"))
      (node (ref "X1") (pin "3") (pinfunction "3_3") (pintype "unspecified"))
      (node (ref "X1") (pin "5") (pinfunction "5_5") (pintype "unspecified"))
      (node (ref "X1") (pin "7") (pinfunction "7_7") (pintype "unspecified"))
      (node (ref "X1") (pin "9") (pinfunction "9_9") (pintype "unspecified"))
      (node (ref "X2") (pin "5") (pinfunction "GND_5") (pintype "unspecified"))
      (node (ref "X2") (pin "6") (pinfunction "SH1_6") (pintype "unspecified"))
      (node (ref "X2") (pin "7") (pinfunction "SH2_7") (pintype "unspecified"))
      (node (ref "X2") (pin "8") (pinfunction "SH3_8") (pintype "unspecified"))
      (node (ref "X2") (pin "9") (pinfunction "SH4_9") (pintype "unspecified"))
      (node (ref "X3") (pin "6") (pinfunction "6_6") (pintype "input"))
      (node (ref "X4") (pin "6") (pinfunction "6_6") (pintype "input"))
      (node (ref "X5") (pin "13") (pinfunction "13_13") (pintype "unspecified"))
      (node (ref "X5") (pin "15") (pinfunction "15_15") (pintype "unspecified"))
      (node (ref "X5") (pin "17") (pinfunction "17_17") (pintype "unspecified"))
      (node (ref "X5") (pin "19") (pinfunction "19_19") (pintype "unspecified"))
      (node (ref "X6") (pin "10") (pinfunction "10_10") (pintype "unspecified"))
      (node (ref "X6") (pin "11") (pinfunction "11_11") (pintype "unspecified"))
      (node (ref "X6") (pin "SH1") (pinfunction "SH1_SH1") (pintype "unspecified"))
      (node (ref "X6") (pin "SH2") (pinfunction "SH2_SH2") (pintype "unspecified"))
    )
    (net (code "63") (name "LEDA") (class "Default")
      (node (ref "R31") (pin "2") (pinfunction "2_2") (pintype "input"))
      (node (ref "X6") (pin "9") (pinfunction "9_9") (pintype "unspecified"))
    )
    (net (code "64") (name "LEDB") (class "Default")
      (node (ref "R32") (pin "2") (pinfunction "2_2") (pintype "input"))
      (node (ref "X6") (pin "12") (pinfunction "12_12") (pintype "unspecified"))
    )
    (net (code "65") (name "Net-(C12-Pad1)") (class "Default")
      (node (ref "C12") (pin "1") (pinfunction "1_1") (pintype "input"))
      (node (ref "KEY1") (pin "1") (pinfunction "1_1") (pintype "unspecified"))
    )
    (net (code "66") (name "Net-(C13-Pad1)") (class "Default")
      (node (ref "C13") (pin "1") (pinfunction "1_1") (pintype "input"))
      (node (ref "KEY2") (pin "1") (pinfunction "1_1") (pintype "unspecified"))
    )
    (net (code "67") (name "Net-(C21-Pad2)") (class "Default")
      (node (ref "C21") (pin "2") (pinfunction "2_2") (pintype "input"))
      (node (ref "KEY3") (pin "2") (pinfunction "2_2") (pintype "unspecified"))
    )
    (net (code "68") (name "Net-(C22-Pad2)") (class "Default")
      (node (ref "C22") (pin "2") (pinfunction "2_2") (pintype "input"))
      (node (ref "KEY4") (pin "3") (pinfunction "3_3") (pintype "unspecified"))
    )
    (net (code "69") (name "Net-(C33-Pad1)") (class "Default")
      (node (ref "C33") (pin "1") (pinfunction "1_1") (pintype "input"))
      (node (ref "R27") (pin "1") (pinfunction "1_1") (pintype "input"))
      (node (ref "R28") (pin "2") (pinfunction "2_2") (pintype "input"))
      (node (ref "X6") (pin "5") (pinfunction "5_5") (pintype "unspecified"))
    )
    (net (code "70") (name "Net-(C34-Pad1)") (class "Default")
      (node (ref "C34") (pin "1") (pinfunction "1_1") (pintype "input"))
      (node (ref "L1") (pin "2") (pinfunction "2_2") (pintype "unspecified"))
      (node (ref "R29") (pin "1") (pinfunction "1_1") (pintype "input"))
      (node (ref "R30") (pin "2") (pinfunction "2_2") (pintype "input"))
      (node (ref "X6") (pin "4") (pinfunction "4_4") (pintype "unspecified"))
    )
    (net (code "71") (name "Net-(D1-A)") (class "Default")
      (node (ref "D1") (pin "2") (pinfunction "A_2") (pintype "unspecified"))
      (node (ref "X2") (pin "1") (pinfunction "VBUS_1") (pintype "unspecified"))
    )
    (net (code "72") (name "Net-(DD1-VDD33)") (class "Default")
      (node (ref "C7") (pin "2") (pinfunction "2_2") (pintype "input"))
      (node (ref "C8") (pin "1") (pinfunction "1_1") (pintype "unspecified"))
      (node (ref "DD1") (pin "2") (pinfunction "VDD33_2") (pintype "unspecified"))
    )
    (net (code "73") (name "Net-(DD2-RXD)") (class "Default")
      (node (ref "DD2") (pin "3") (pinfunction "RXD_3") (pintype "unspecified"))
      (node (ref "R18") (pin "1") (pinfunction "1_1") (pintype "input"))
    )
    (net (code "74") (name "Net-(DD2-TXD)") (class "Default")
      (node (ref "DD2") (pin "2") (pinfunction "TXD_2") (pintype "unspecified"))
      (node (ref "R19") (pin "1") (pinfunction "1_1") (pintype "input"))
    )
    (net (code "75") (name "Net-(DD2-UD+)") (class "Default")
      (node (ref "DD2") (pin "5") (pinfunction "UD+_5") (pintype "unspecified"))
      (node (ref "X2") (pin "3") (pinfunction "D+_3") (pintype "unspecified"))
    )
    (net (code "76") (name "Net-(DD2-UD-)") (class "Default")
      (node (ref "DD2") (pin "6") (pinfunction "UD-_6") (pintype "unspecified"))
      (node (ref "X2") (pin "2") (pinfunction "D-_2") (pintype "unspecified"))
    )
    (net (code "77") (name "Net-(DD2-V3)") (class "Default")
      (node (ref "C14") (pin "2") (pinfunction "2_2") (pintype "input"))
      (node (ref "DD2") (pin "4") (pinfunction "V3_4") (pintype "unspecified"))
    )
    (net (code "78") (name "Net-(DD2-XI)") (class "Default")
      (node (ref "C15") (pin "2") (pinfunction "2_2") (pintype "input"))
      (node (ref "DD2") (pin "7") (pinfunction "XI_7") (pintype "unspecified"))
      (node (ref "ZQ1") (pin "1") (pinfunction "1_1") (pintype "unspecified"))
    )
    (net (code "79") (name "Net-(DD2-XO)") (class "Default")
      (node (ref "C16") (pin "2") (pinfunction "2_2") (pintype "input"))
      (node (ref "DD2") (pin "8") (pinfunction "XO_8") (pintype "unspecified"))
      (node (ref "ZQ1") (pin "2") (pinfunction "2_2") (pintype "unspecified"))
    )
    (net (code "80") (name "Net-(DD3-AREF)") (class "Default")
      (node (ref "C29") (pin "2") (pinfunction "2_2") (pintype "input"))
      (node (ref "DD3") (pin "62") (pinfunction "AREF_62") (pintype "unspecified"))
    )
    (net (code "81") (name "Net-(DD3-XTAL1)") (class "Default")
      (node (ref "C24") (pin "2") (pinfunction "2_2") (pintype "input"))
      (node (ref "DD3") (pin "24") (pinfunction "XTAL1_24") (pintype "unspecified"))
      (node (ref "ZQ2") (pin "1") (pinfunction "OSC1_1") (pintype "input"))
    )
    (net (code "82") (name "Net-(DD3-XTAL2)") (class "Default")
      (node (ref "C23") (pin "1") (pinfunction "1_1") (pintype "input"))
      (node (ref "DD3") (pin "23") (pinfunction "XTAL2_23") (pintype "unspecified"))
      (node (ref "ZQ2") (pin "2") (pinfunction "OSC2_2") (pintype "input"))
    )
    (net (code "83") (name "Net-(DD4-LEDA)") (class "Default")
      (node (ref "DD4") (pin "27") (pinfunction "LEDA_27") (pintype "unspecified"))
      (node (ref "R31") (pin "1") (pinfunction "1_1") (pintype "input"))
    )
    (net (code "84") (name "Net-(DD4-LEDB)") (class "Default")
      (node (ref "DD4") (pin "26") (pinfunction "LEDB_26") (pintype "unspecified"))
      (node (ref "R32") (pin "1") (pinfunction "1_1") (pintype "input"))
    )
    (net (code "85") (name "Net-(DD4-OSC1)") (class "Default")
      (node (ref "C31") (pin "1") (pinfunction "1_1") (pintype "input"))
      (node (ref "DD4") (pin "23") (pinfunction "OSC1_23") (pintype "unspecified"))
      (node (ref "ZQ3") (pin "1") (pinfunction "1_1") (pintype "unspecified"))
    )
    (net (code "86") (name "Net-(DD4-OSC2)") (class "Default")
      (node (ref "C32") (pin "1") (pinfunction "1_1") (pintype "input"))
      (node (ref "DD4") (pin "24") (pinfunction "OSC2_24") (pintype "unspecified"))
      (node (ref "ZQ3") (pin "2") (pinfunction "2_2") (pintype "unspecified"))
    )
    (net (code "87") (name "Net-(DD4-RBIAS)") (class "Default")
      (node (ref "DD4") (pin "14") (pinfunction "RBIAS_14") (pintype "unspecified"))
      (node (ref "R24") (pin "2") (pinfunction "2_2") (pintype "unspecified"))
    )
    (net (code "88") (name "Net-(DD4-VCAP)") (class "Default")
      (node (ref "C30") (pin "1") (pinfunction "1_1") (pintype "input"))
      (node (ref "DD4") (pin "1") (pinfunction "VCAP_1") (pintype "unspecified"))
    )
    (net (code "89") (name "Net-(H1-Pad2)") (class "Default")
      (node (ref "H1") (pin "2") (pinfunction "2_2") (pintype "unspecified"))
      (node (ref "R17") (pin "1") (pinfunction "1_1") (pintype "input"))
    )
    (net (code "90") (name "Net-(LED1-A)") (class "Default")
      (node (ref "LED1") (pin "1") (pinfunction "A_1") (pintype "unspecified"))
      (node (ref "R20") (pin "1") (pinfunction "1_1") (pintype "input"))
    )
    (net (code "91") (name "Net-(LED2-K)") (class "Default")
      (node (ref "LED2") (pin "2") (pinfunction "K_2") (pintype "unspecified"))
      (node (ref "R22") (pin "2") (pinfunction "2_2") (pintype "input"))
    )
    (net (code "92") (name "Net-(LED3-K)") (class "Default")
      (node (ref "LED3") (pin "2") (pinfunction "K_2") (pintype "unspecified"))
      (node (ref "R23") (pin "2") (pinfunction "2_2") (pintype "input"))
    )
    (net (code "93") (name "Net-(R2-Pad1)") (class "Default")
      (node (ref "R2") (pin "1") (pinfunction "1_1") (pintype "input"))
      (node (ref "X1") (pin "4") (pinfunction "4_4") (pintype "unspecified"))
    )
    (net (code "94") (name "Net-(R3-Pad2)") (class "Default")
      (node (ref "R3") (pin "2") (pinfunction "2_2") (pintype "input"))
      (node (ref "X1") (pin "14") (pinfunction "14_14") (pintype "unspecified"))
    )
    (net (code "95") (name "Net-(R6-Pad1)") (class "Default")
      (node (ref "R6") (pin "1") (pinfunction "1_1") (pintype "input"))
      (node (ref "X1") (pin "6") (pinfunction "6_6") (pintype "unspecified"))
    )
    (net (code "96") (name "Net-(R7-Pad2)") (class "Default")
      (node (ref "R7") (pin "2") (pinfunction "2_2") (pintype "input"))
      (node (ref "X1") (pin "12") (pinfunction "12_12") (pintype "unspecified"))
    )
    (net (code "97") (name "Net-(R10-Pad1)") (class "Default")
      (node (ref "R10") (pin "1") (pinfunction "1_1") (pintype "input"))
      (node (ref "X1") (pin "8") (pinfunction "8_8") (pintype "unspecified"))
    )
    (net (code "98") (name "Net-(R11-Pad2)") (class "Default")
      (node (ref "R11") (pin "2") (pinfunction "2_2") (pintype "input"))
      (node (ref "X1") (pin "10") (pinfunction "10_10") (pintype "unspecified"))
    )
    (net (code "99") (name "Net-(R14-Pad2)") (class "Default")
      (node (ref "R14") (pin "2") (pinfunction "2_2") (pintype "input"))
      (node (ref "VT1") (pin "1") (pinfunction "1_1") (pintype "input"))
    )
    (net (code "100") (name "Net-(R15-Pad1)") (class "Default")
      (node (ref "R15") (pin "1") (pinfunction "1_1") (pintype "input"))
      (node (ref "VT2") (pin "1") (pinfunction "1_1") (pintype "input"))
    )
    (net (code "101") (name "RESET") (class "Default")
      (node (ref "DD4") (pin "10") (pinfunction "RESET#_10") (pintype "unspecified"))
      (node (ref "H3") (pin "2") (pinfunction "2_2") (pintype "unspecified"))
      (node (ref "R25") (pin "1") (pinfunction "1_1") (pintype "unspecified"))
    )
    (net (code "102") (name "RTS") (class "Default")
      (node (ref "DD2") (pin "14") (pinfunction "RTS#_14") (pintype "unspecified"))
      (node (ref "R15") (pin "2") (pinfunction "2_2") (pintype "input"))
      (node (ref "VT1") (pin "2") (pinfunction "2_2") (pintype "input"))
    )
    (net (code "103") (name "TPIN+") (class "Default")
      (node (ref "DD4") (pin "13") (pinfunction "TPIN+_13") (pintype "unspecified"))
      (node (ref "R28") (pin "1") (pinfunction "1_1") (pintype "input"))
      (node (ref "X6") (pin "3") (pinfunction "RD+_3") (pintype "unspecified"))
    )
    (net (code "104") (name "TPIN-") (class "Default")
      (node (ref "DD4") (pin "12") (pinfunction "TPIN-_12") (pintype "unspecified"))
      (node (ref "R27") (pin "2") (pinfunction "2_2") (pintype "input"))
      (node (ref "X6") (pin "6") (pinfunction "RD-_6") (pintype "unspecified"))
    )
    (net (code "105") (name "TPOUT+") (class "Default")
      (node (ref "DD4") (pin "17") (pinfunction "TPOUT+_17") (pintype "unspecified"))
      (node (ref "R30") (pin "1") (pinfunction "1_1") (pintype "input"))
      (node (ref "X6") (pin "1") (pinfunction "TD+_1") (pintype "unspecified"))
    )
    (net (code "106") (name "TPOUT-") (class "Default")
      (node (ref "DD4") (pin "16") (pinfunction "TPOUT-_16") (pintype "unspecified"))
      (node (ref "R29") (pin "2") (pinfunction "2_2") (pintype "input"))
      (node (ref "X6") (pin "2") (pinfunction "TD-_2") (pintype "unspecified"))
    )
    (net (code "107") (name "unconnected-(DD1-CLK-Pad20)") (class "Default")
      (node (ref "DD1") (pin "20") (pinfunction "CLK_20") (pintype "unspecified"))
    )
    (net (code "108") (name "unconnected-(DD1-CMD-Pad19)") (class "Default")
      (node (ref "DD1") (pin "19") (pinfunction "CMD_19") (pintype "unspecified"))
    )
    (net (code "109") (name "unconnected-(DD1-IO2-Pad24)") (class "Default")
      (node (ref "DD1") (pin "24") (pinfunction "IO2_24") (pintype "unspecified"))
    )
    (net (code "110") (name "unconnected-(DD1-IO13-Pad16)") (class "Default")
      (node (ref "DD1") (pin "16") (pinfunction "IO13_16") (pintype "unspecified"))
    )
    (net (code "111") (name "unconnected-(DD1-IO15-Pad23)") (class "Default")
      (node (ref "DD1") (pin "23") (pinfunction "IO15_23") (pintype "unspecified"))
    )
    (net (code "112") (name "unconnected-(DD1-NC-Pad32)") (class "Default")
      (node (ref "DD1") (pin "32") (pinfunction "NC_32") (pintype "unspecified"))
    )
    (net (code "113") (name "unconnected-(DD1-SD0-Pad21)") (class "Default")
      (node (ref "DD1") (pin "21") (pinfunction "SD0_21") (pintype "unspecified"))
    )
    (net (code "114") (name "unconnected-(DD1-SD1-Pad22)") (class "Default")
      (node (ref "DD1") (pin "22") (pinfunction "SD1_22") (pintype "unspecified"))
    )
    (net (code "115") (name "unconnected-(DD1-SD2-Pad17)") (class "Default")
      (node (ref "DD1") (pin "17") (pinfunction "SD2_17") (pintype "unspecified"))
    )
    (net (code "116") (name "unconnected-(DD1-SD3-Pad18)") (class "Default")
      (node (ref "DD1") (pin "18") (pinfunction "SD3_18") (pintype "unspecified"))
    )
    (net (code "117") (name "unconnected-(DD2-CTS#-Pad9)") (class "Default")
      (node (ref "DD2") (pin "9") (pinfunction "CTS#_9") (pintype "unspecified"))
    )
    (net (code "118") (name "unconnected-(DD2-DCD#-Pad12)") (class "Default")
      (node (ref "DD2") (pin "12") (pinfunction "DCD#_12") (pintype "unspecified"))
    )
    (net (code "119") (name "unconnected-(DD2-DSR#-Pad10)") (class "Default")
      (node (ref "DD2") (pin "10") (pinfunction "DSR#_10") (pintype "unspecified"))
    )
    (net (code "120") (name "unconnected-(DD2-R232-Pad15)") (class "Default")
      (node (ref "DD2") (pin "15") (pinfunction "R232_15") (pintype "unspecified"))
    )
    (net (code "121") (name "unconnected-(DD2-RI-Pad11)") (class "Default")
      (node (ref "DD2") (pin "11") (pinfunction "RI_11") (pintype "unspecified"))
    )
    (net (code "122") (name "unconnected-(DD3-(ICP1)PD4-Pad29)") (class "Default")
      (node (ref "DD3") (pin "29") (pinfunction "(ICP1)PD4_29") (pintype "unspecified"))
    )
    (net (code "123") (name "unconnected-(DD3-(ICP3{slash}INT7)PE7-Pad9)") (class "Default")
      (node (ref "DD3") (pin "9") (pinfunction "(ICP3/INT7)PE7_9") (pintype "unspecified"))
    )
    (net (code "124") (name "unconnected-(DD3-(OC2{slash}OC1C)PB7-Pad17)") (class "Default")
      (node (ref "DD3") (pin "17") (pinfunction "(OC2/OC1C)PB7_17") (pintype "unspecified"))
    )
    (net (code "125") (name "unconnected-(DD3-(OC3A{slash}AIN1)PE3-Pad5)") (class "Default")
      (node (ref "DD3") (pin "5") (pinfunction "(OC3A/AIN1)PE3_5") (pintype "unspecified"))
    )
    (net (code "126") (name "unconnected-(DD3-(SCL{slash}INT0)PD0-Pad25)") (class "Default")
      (node (ref "DD3") (pin "25") (pinfunction "(SCL/INT0)PD0_25") (pintype "unspecified"))
    )
    (net (code "127") (name "unconnected-(DD3-(SDA{slash}INT1)PD1-Pad26)") (class "Default")
      (node (ref "DD3") (pin "26") (pinfunction "(SDA/INT1)PD1_26") (pintype "unspecified"))
    )
    (net (code "128") (name "unconnected-(DD3-(SS#)PB0-Pad10)") (class "Default")
      (node (ref "DD3") (pin "10") (pinfunction "(SS#)PB0_10") (pintype "unspecified"))
    )
    (net (code "129") (name "unconnected-(DD3-(T3{slash}INT6)PE6-Pad8)") (class "Default")
      (node (ref "DD3") (pin "8") (pinfunction "(T3/INT6)PE6_8") (pintype "unspecified"))
    )
    (net (code "130") (name "unconnected-(DD3-(XCK0{slash}AIN0)PE2-Pad4)") (class "Default")
      (node (ref "DD3") (pin "4") (pinfunction "(XCK0/AIN0)PE2_4") (pintype "unspecified"))
    )
    (net (code "131") (name "unconnected-(DD3-(XCK1)PD5-Pad30)") (class "Default")
      (node (ref "DD3") (pin "30") (pinfunction "(XCK1)PD5_30") (pintype "unspecified"))
    )
    (net (code "132") (name "unconnected-(DD3-PA0(AD0)-Pad51)") (class "Default")
      (node (ref "DD3") (pin "51") (pinfunction "PA0(AD0)_51") (pintype "unspecified"))
    )
    (net (code "133") (name "unconnected-(DD3-PA1(AD1)-Pad50)") (class "Default")
      (node (ref "DD3") (pin "50") (pinfunction "PA1(AD1)_50") (pintype "unspecified"))
    )
    (net (code "134") (name "unconnected-(DD3-PA2(AD2)-Pad49)") (class "Default")
      (node (ref "DD3") (pin "49") (pinfunction "PA2(AD2)_49") (pintype "unspecified"))
    )
    (net (code "135") (name "unconnected-(DD3-PA3(AD3)-Pad48)") (class "Default")
      (node (ref "DD3") (pin "48") (pinfunction "PA3(AD3)_48") (pintype "unspecified"))
    )
    (net (code "136") (name "unconnected-(DD3-PA4(AD4)-Pad47)") (class "Default")
      (node (ref "DD3") (pin "47") (pinfunction "PA4(AD4)_47") (pintype "unspecified"))
    )
    (net (code "137") (name "unconnected-(DD3-PA5(AD5)-Pad46)") (class "Default")
      (node (ref "DD3") (pin "46") (pinfunction "PA5(AD5)_46") (pintype "unspecified"))
    )
    (net (code "138") (name "unconnected-(DD3-PA6(AD6)-Pad45)") (class "Default")
      (node (ref "DD3") (pin "45") (pinfunction "PA6(AD6)_45") (pintype "unspecified"))
    )
    (net (code "139") (name "unconnected-(DD3-PEN#-Pad1)") (class "Default")
      (node (ref "DD3") (pin "1") (pinfunction "PEN#_1") (pintype "unspecified"))
    )
    (net (code "140") (name "unconnected-(DD3-PF5(ADC5{slash}TMS)-Pad56)") (class "Default")
      (node (ref "DD3") (pin "56") (pinfunction "PF5(ADC5/TMS)_56") (pintype "unspecified"))
    )
    (net (code "141") (name "unconnected-(DD3-PF6(ADC6{slash}TDO)-Pad55)") (class "Default")
      (node (ref "DD3") (pin "55") (pinfunction "PF6(ADC6/TDO)_55") (pintype "unspecified"))
    )
    (net (code "142") (name "unconnected-(DD3-PF7(ADC7{slash}TDI)-Pad54)") (class "Default")
      (node (ref "DD3") (pin "54") (pinfunction "PF7(ADC7/TDI)_54") (pintype "unspecified"))
    )
    (net (code "143") (name "unconnected-(DD3-TOSC1{slash}PG4-Pad19)") (class "Default")
      (node (ref "DD3") (pin "19") (pinfunction "TOSC1/PG4_19") (pintype "unspecified"))
    )
    (net (code "144") (name "unconnected-(DD3-TOSC2{slash}PG3-Pad18)") (class "Default")
      (node (ref "DD3") (pin "18") (pinfunction "TOSC2/PG3_18") (pintype "unspecified"))
    )
    (net (code "145") (name "unconnected-(DD4-NC-Pad5)") (class "Default")
      (node (ref "DD4") (pin "5") (pinfunction "NC_5") (pintype "unspecified"))
    )
    (net (code "146") (name "unconnected-(KEY1-Pad3)") (class "Default")
      (node (ref "KEY1") (pin "3") (pinfunction "3_3") (pintype "unspecified"))
    )
    (net (code "147") (name "unconnected-(KEY2-Pad3)") (class "Default")
      (node (ref "KEY2") (pin "3") (pinfunction "3_3") (pintype "unspecified"))
    )
    (net (code "148") (name "unconnected-(KEY3-Pad1)") (class "Default")
      (node (ref "KEY3") (pin "1") (pinfunction "1_1") (pintype "unspecified"))
    )
    (net (code "149") (name "unconnected-(KEY4-Pad4)") (class "Default")
      (node (ref "KEY4") (pin "4") (pinfunction "4_4") (pintype "unspecified"))
    )
    (net (code "150") (name "unconnected-(KEY5-Pad2)") (class "Default")
      (node (ref "KEY5") (pin "2") (pinfunction "2_2") (pintype "unspecified"))
    )
    (net (code "151") (name "unconnected-(KEY5-Pad4)") (class "Default")
      (node (ref "KEY5") (pin "4") (pinfunction "4_4") (pintype "unspecified"))
    )
    (net (code "152") (name "unconnected-(U1-A3-Pad4)") (class "Default")
      (node (ref "U1") (pin "4") (pinfunction "A3_4") (pintype "unspecified"))
    )
    (net (code "153") (name "unconnected-(U1-A4-Pad5)") (class "Default")
      (node (ref "U1") (pin "5") (pinfunction "A4_5") (pintype "unspecified"))
    )
    (net (code "154") (name "unconnected-(U1-A5-Pad6)") (class "Default")
      (node (ref "U1") (pin "6") (pinfunction "A5_6") (pintype "unspecified"))
    )
    (net (code "155") (name "unconnected-(U1-A6-Pad7)") (class "Default")
      (node (ref "U1") (pin "7") (pinfunction "A6_7") (pintype "unspecified"))
    )
    (net (code "156") (name "unconnected-(U1-A7-Pad8)") (class "Default")
      (node (ref "U1") (pin "8") (pinfunction "A7_8") (pintype "unspecified"))
    )
    (net (code "157") (name "unconnected-(U1-A8-Pad9)") (class "Default")
      (node (ref "U1") (pin "9") (pinfunction "A8_9") (pintype "unspecified"))
    )
    (net (code "158") (name "unconnected-(U1-B3-Pad17)") (class "Default")
      (node (ref "U1") (pin "17") (pinfunction "B3_17") (pintype "unspecified"))
    )
    (net (code "159") (name "unconnected-(U1-B4-Pad16)") (class "Default")
      (node (ref "U1") (pin "16") (pinfunction "B4_16") (pintype "unspecified"))
    )
    (net (code "160") (name "unconnected-(U1-B5-Pad15)") (class "Default")
      (node (ref "U1") (pin "15") (pinfunction "B5_15") (pintype "unspecified"))
    )
    (net (code "161") (name "unconnected-(U1-B6-Pad14)") (class "Default")
      (node (ref "U1") (pin "14") (pinfunction "B6_14") (pintype "unspecified"))
    )
    (net (code "162") (name "unconnected-(U1-B7-Pad13)") (class "Default")
      (node (ref "U1") (pin "13") (pinfunction "B7_13") (pintype "unspecified"))
    )
    (net (code "163") (name "unconnected-(U1-B8-Pad12)") (class "Default")
      (node (ref "U1") (pin "12") (pinfunction "B8_12") (pintype "unspecified"))
    )
    (net (code "164") (name "unconnected-(X2-ID-Pad4)") (class "Default")
      (node (ref "X2") (pin "4") (pinfunction "ID_4") (pintype "unspecified"))
    )
    (net (code "165") (name "unconnected-(X6-CHS_GND-Pad8)") (class "Default")
      (node (ref "X6") (pin "8") (pinfunction "CHS_GND_8") (pintype "unspecified"))
    )
    (net (code "166") (name "unconnected-(X6-NC-Pad7)") (class "Default")
      (node (ref "X6") (pin "7") (pinfunction "NC_7") (pintype "unspecified"))
    )
  )
)
